# ESC.net
KiCad netlist of a schematic drawn in EAGLE
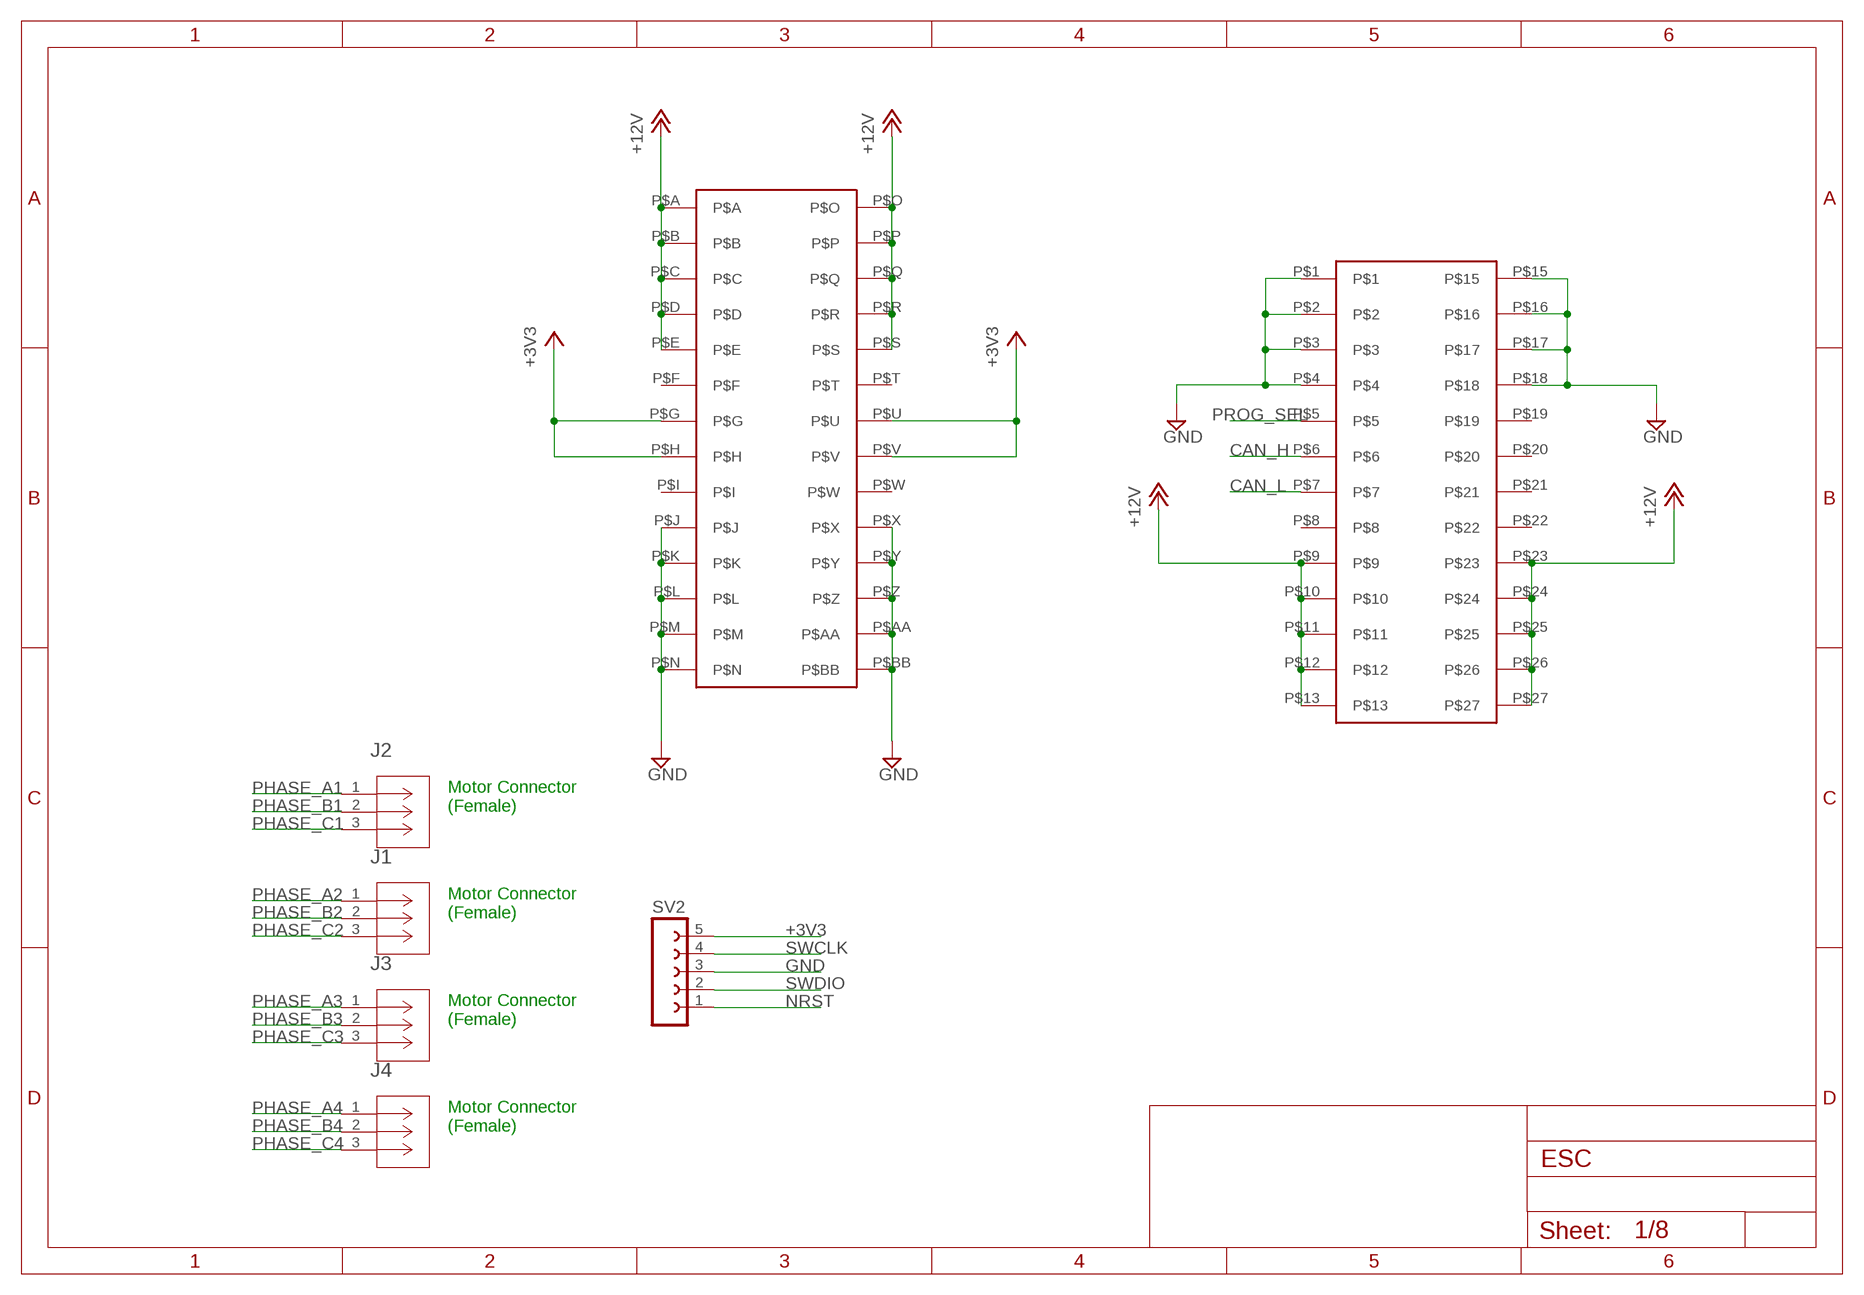
[diagram p0: schematic, sheet 1]
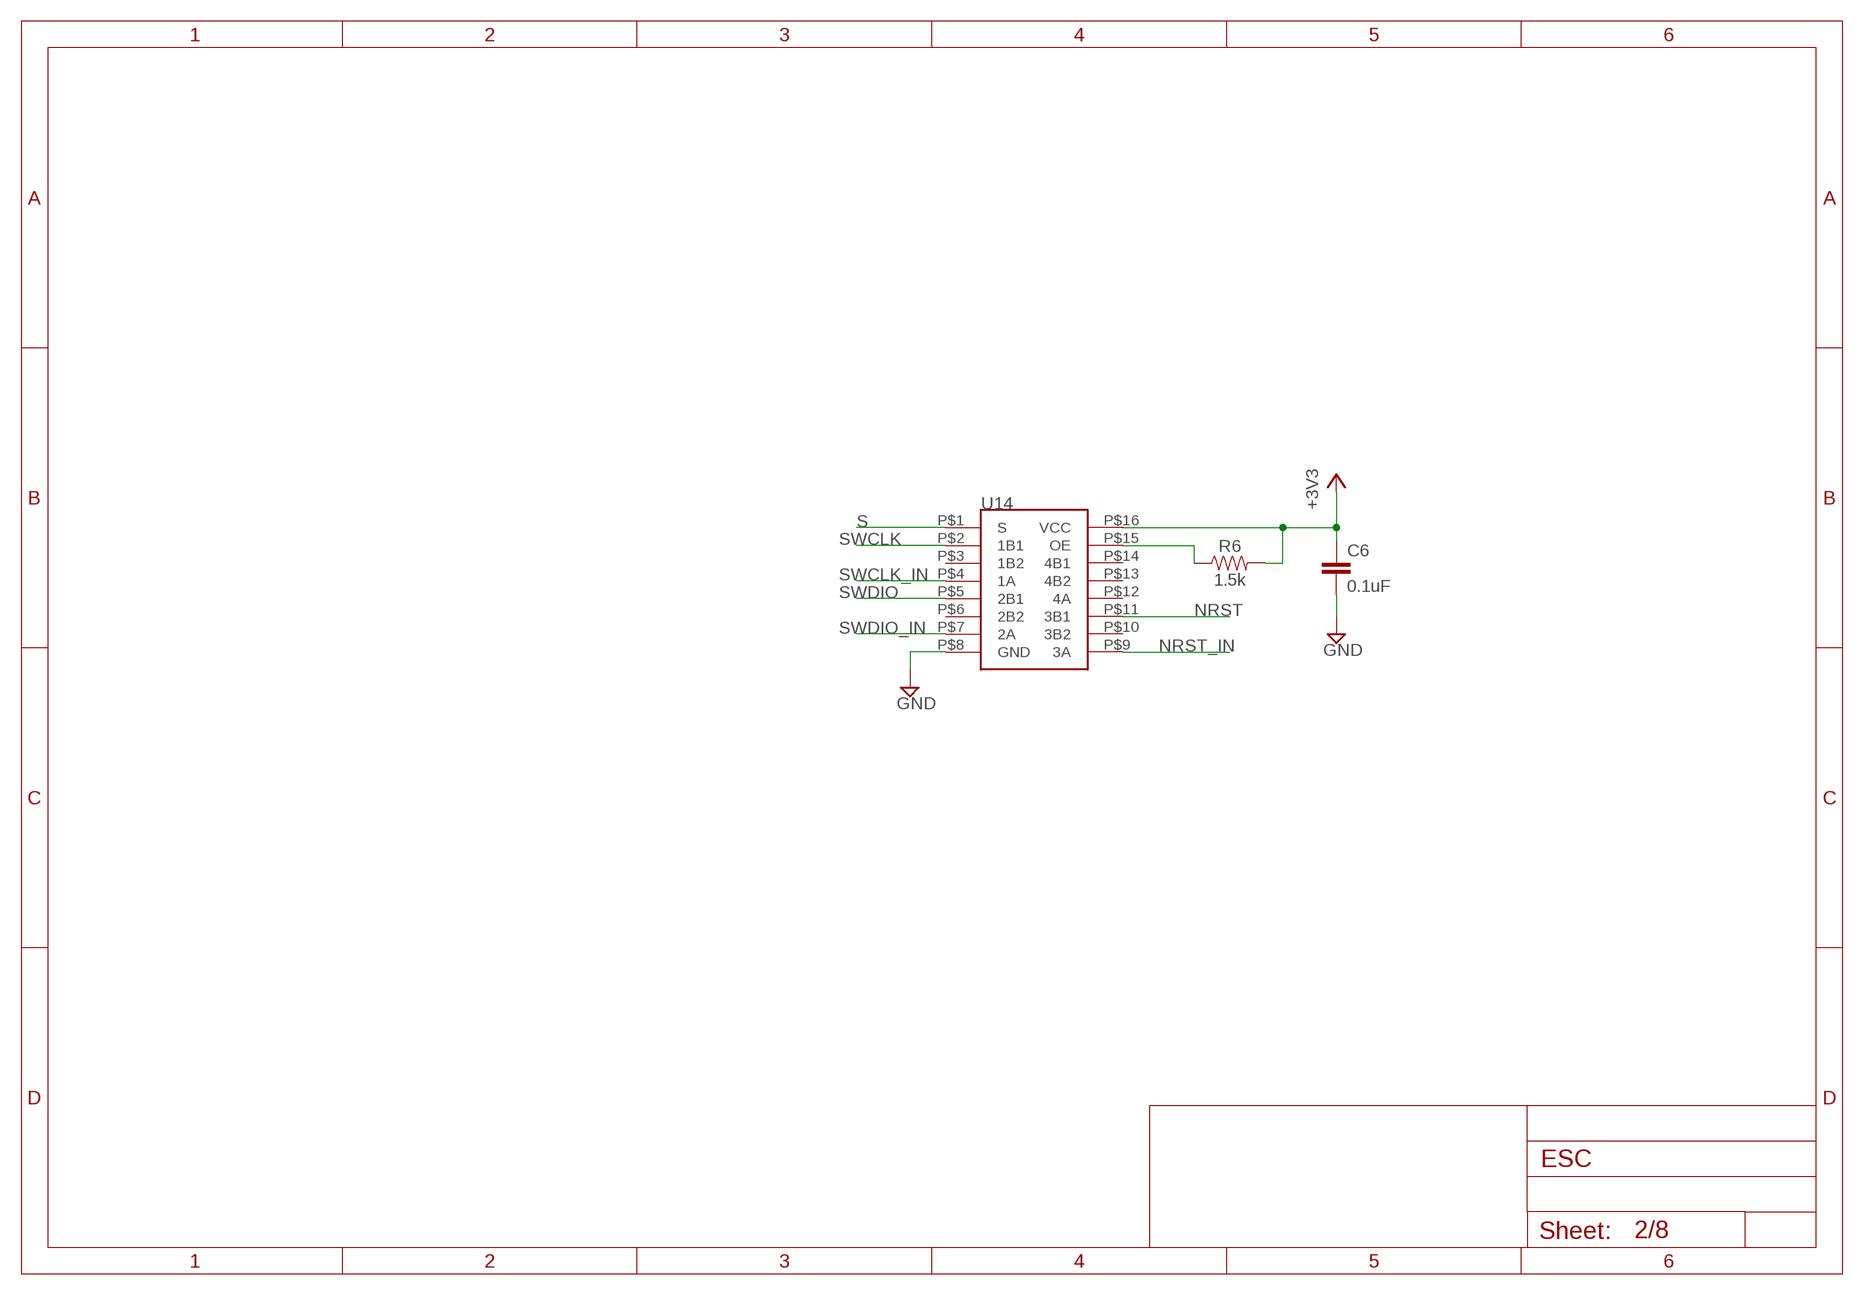
[diagram p1: schematic, sheet 2]
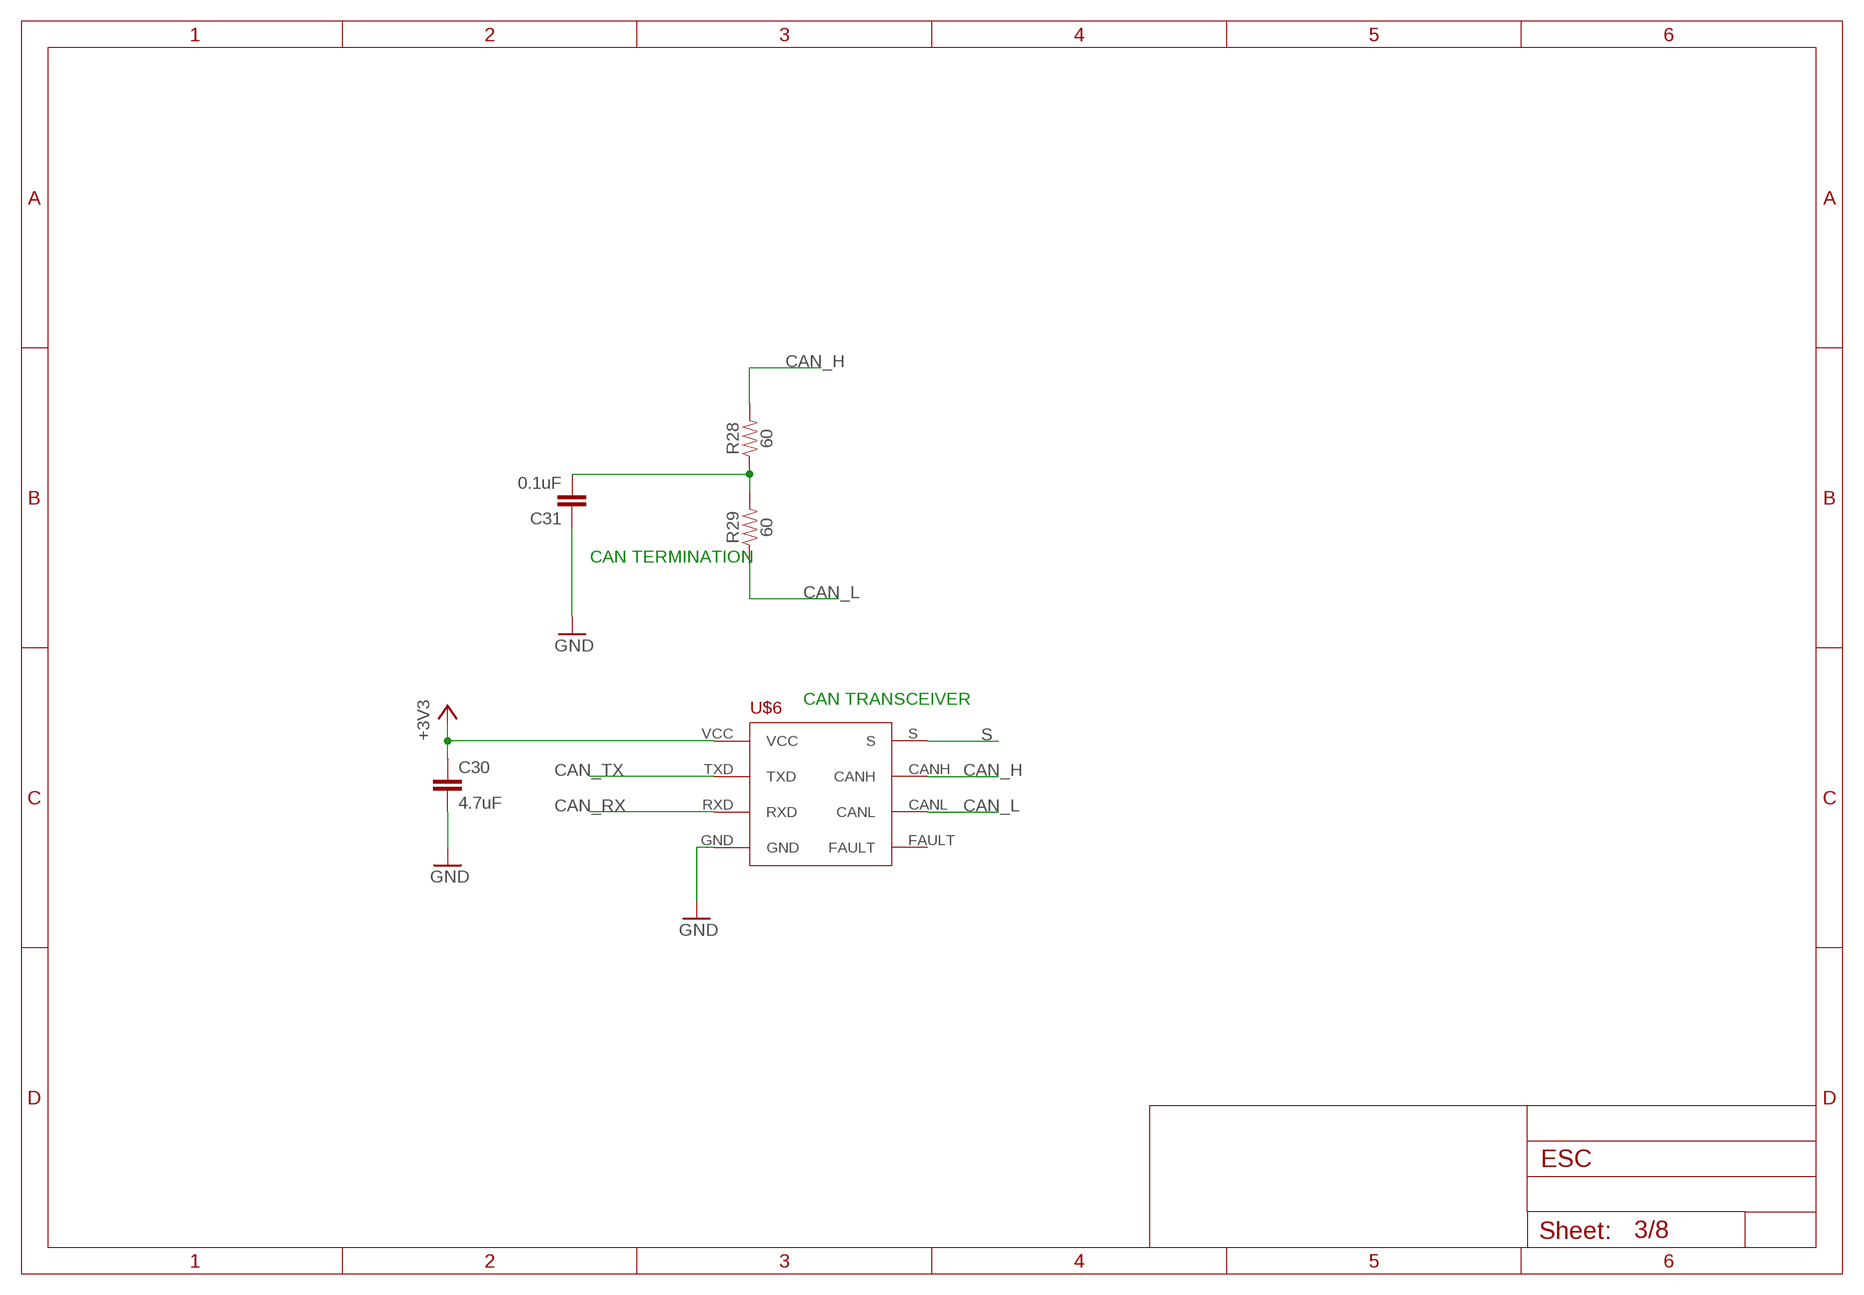
[diagram p2: schematic, sheet 3]
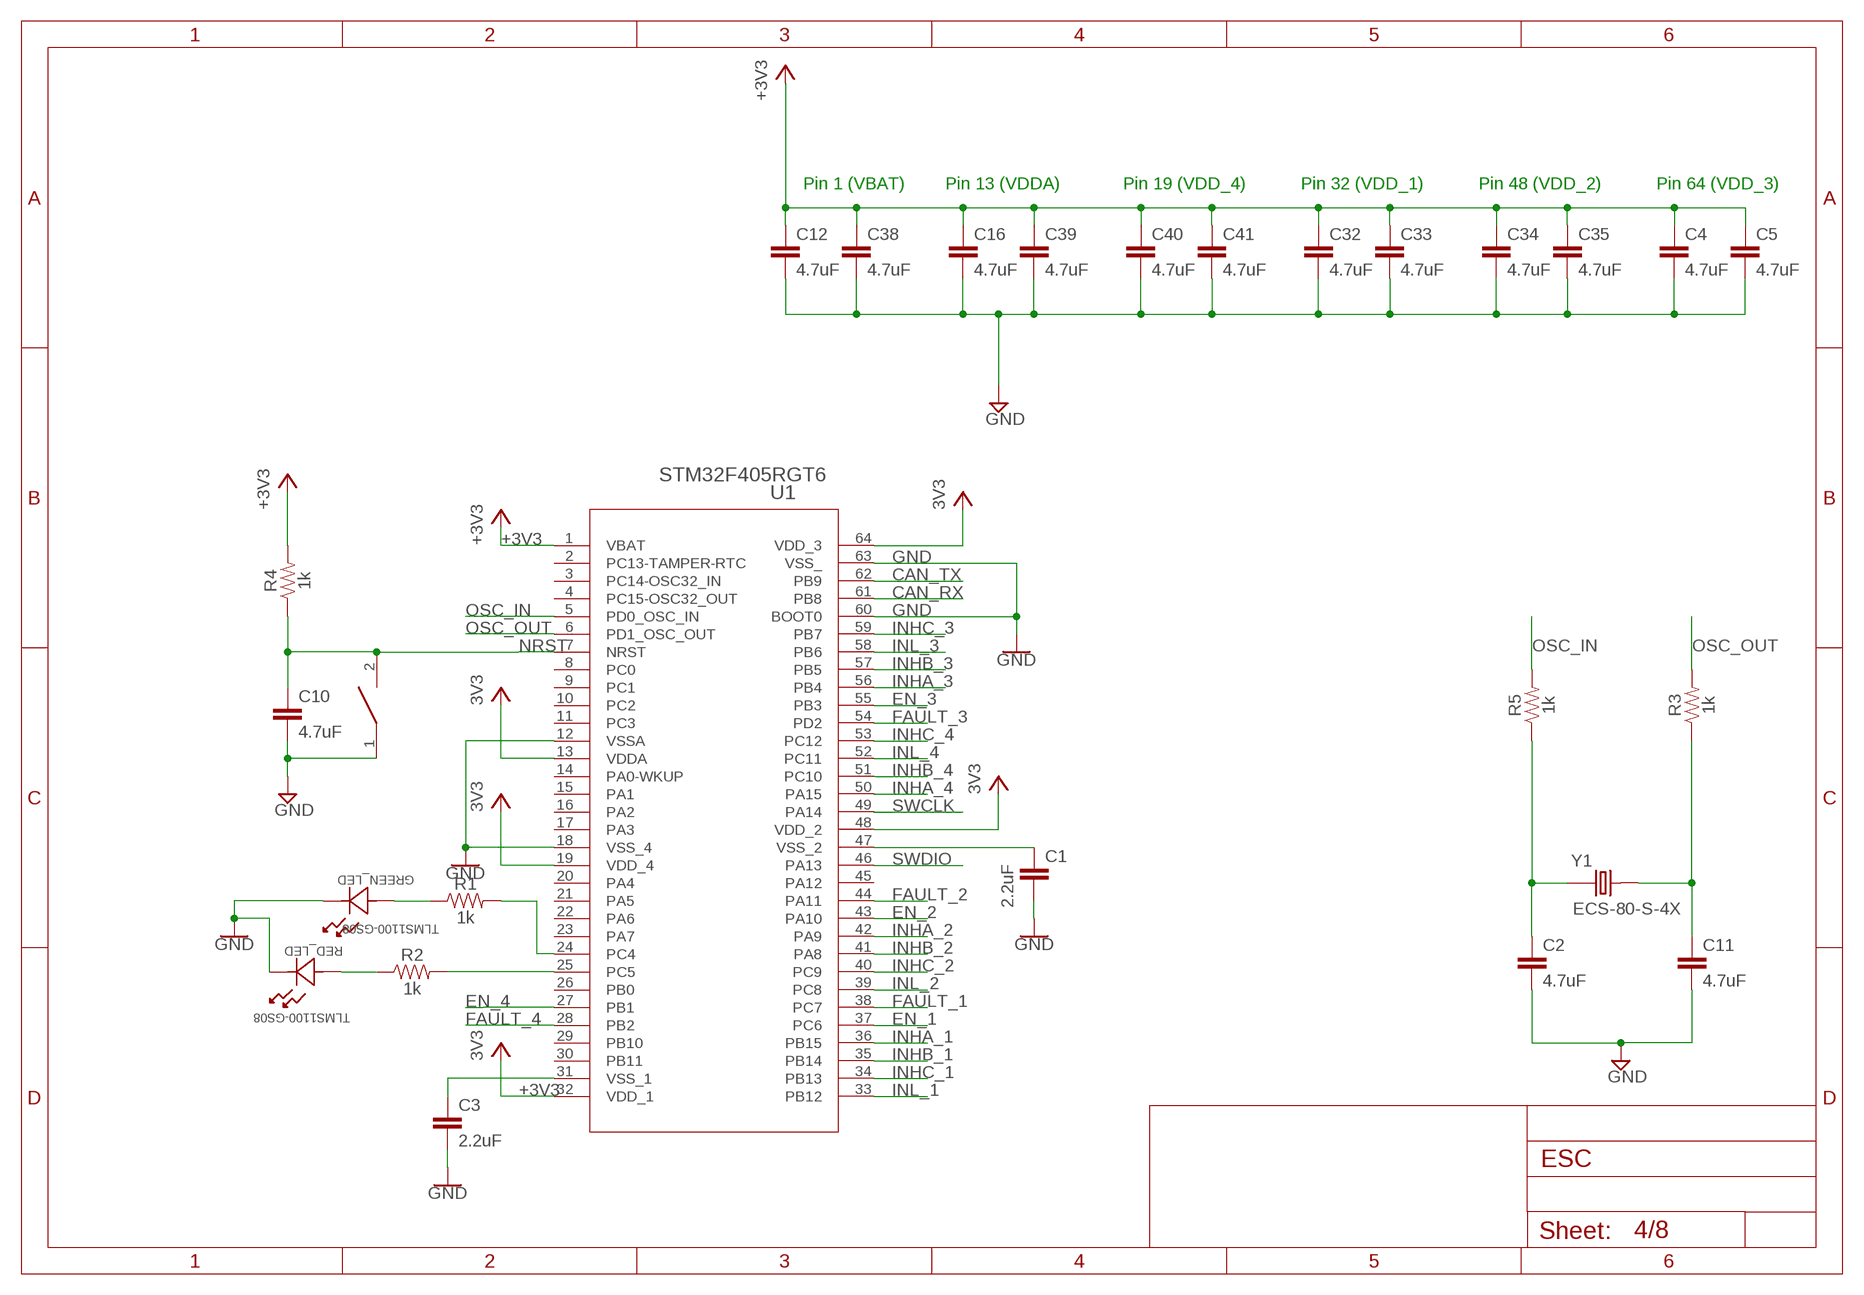
[diagram p3: schematic, sheet 4]
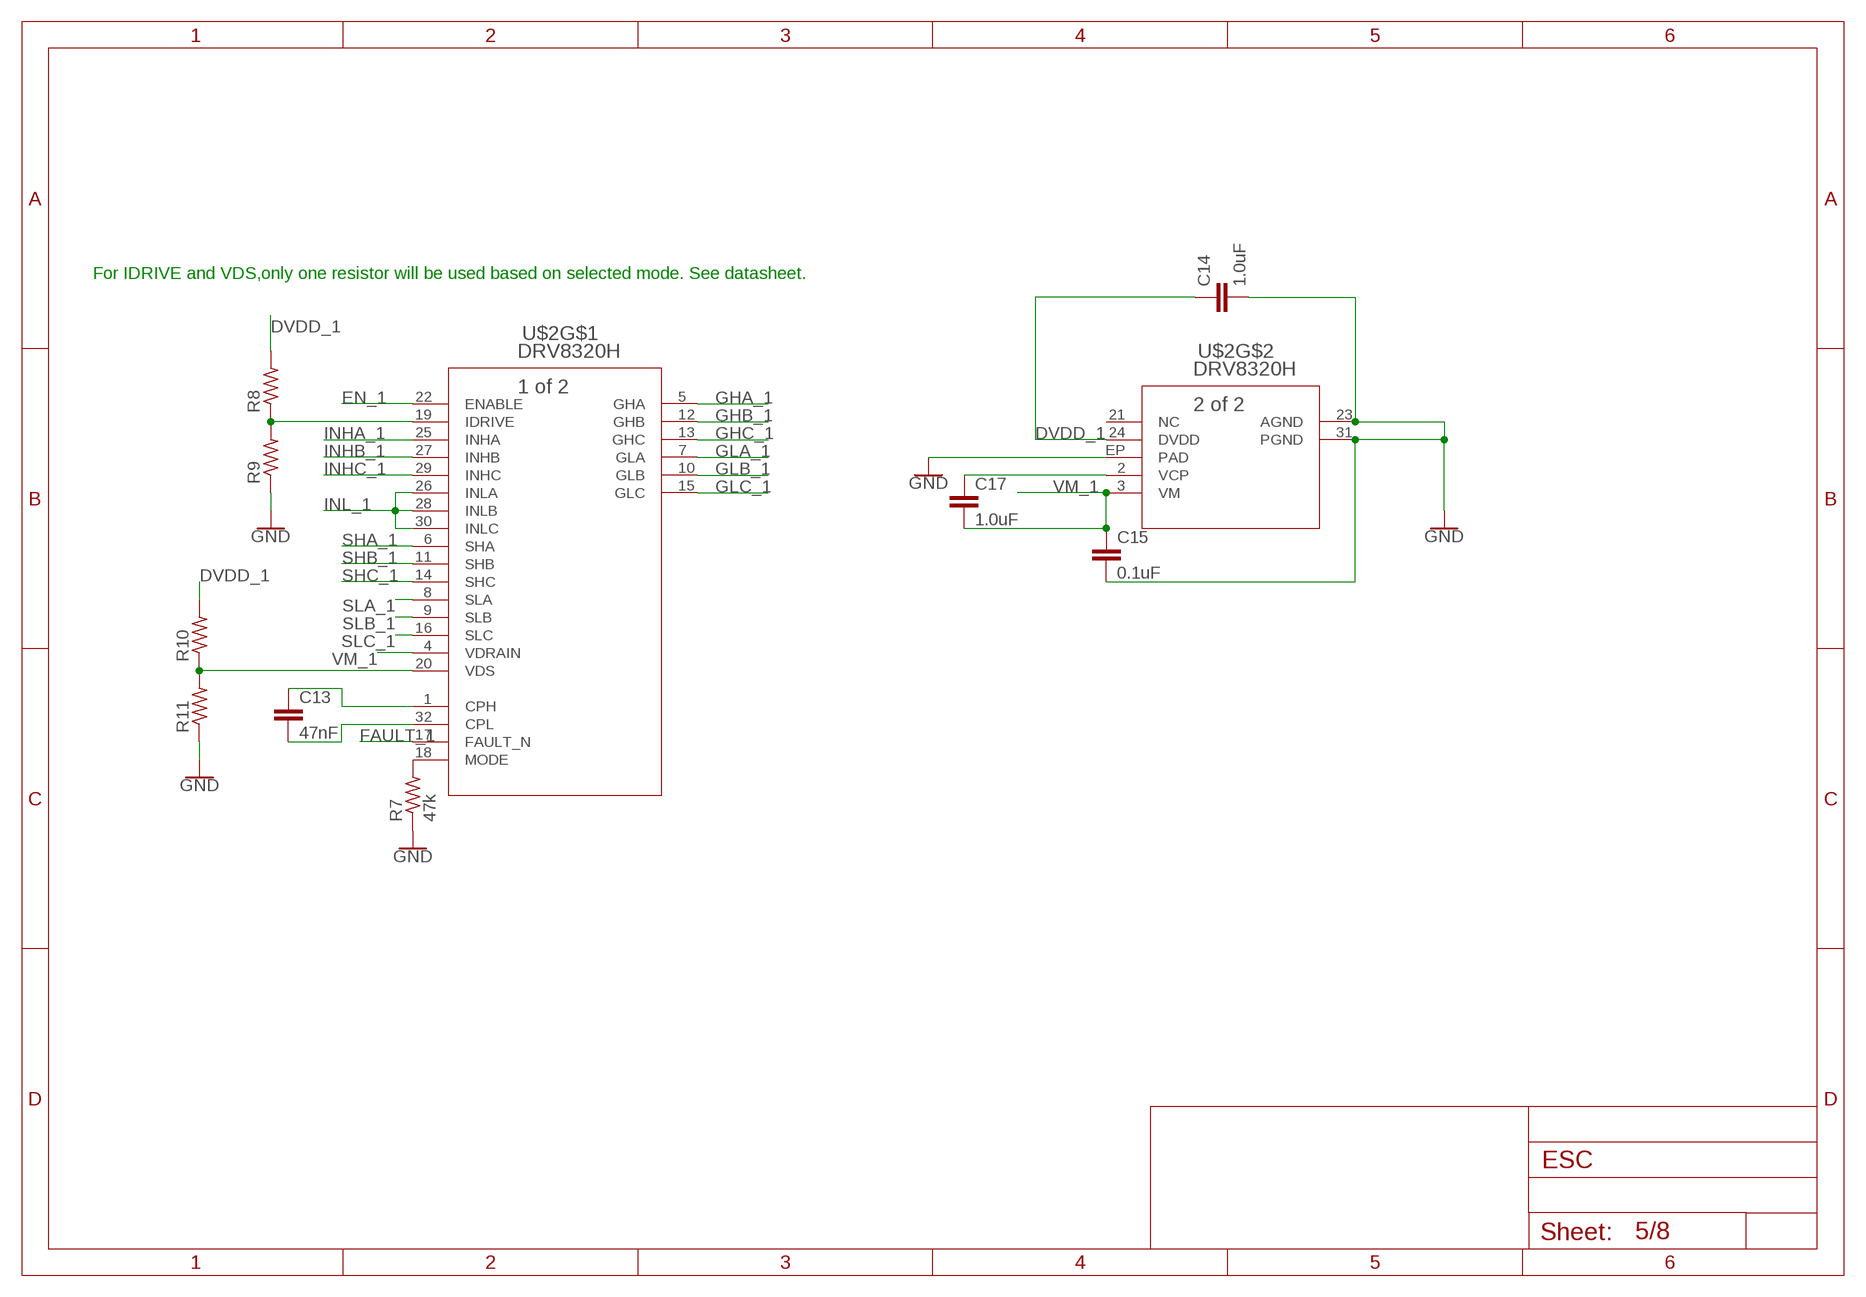
[diagram p4: schematic, sheet 5, part 1 of 2]
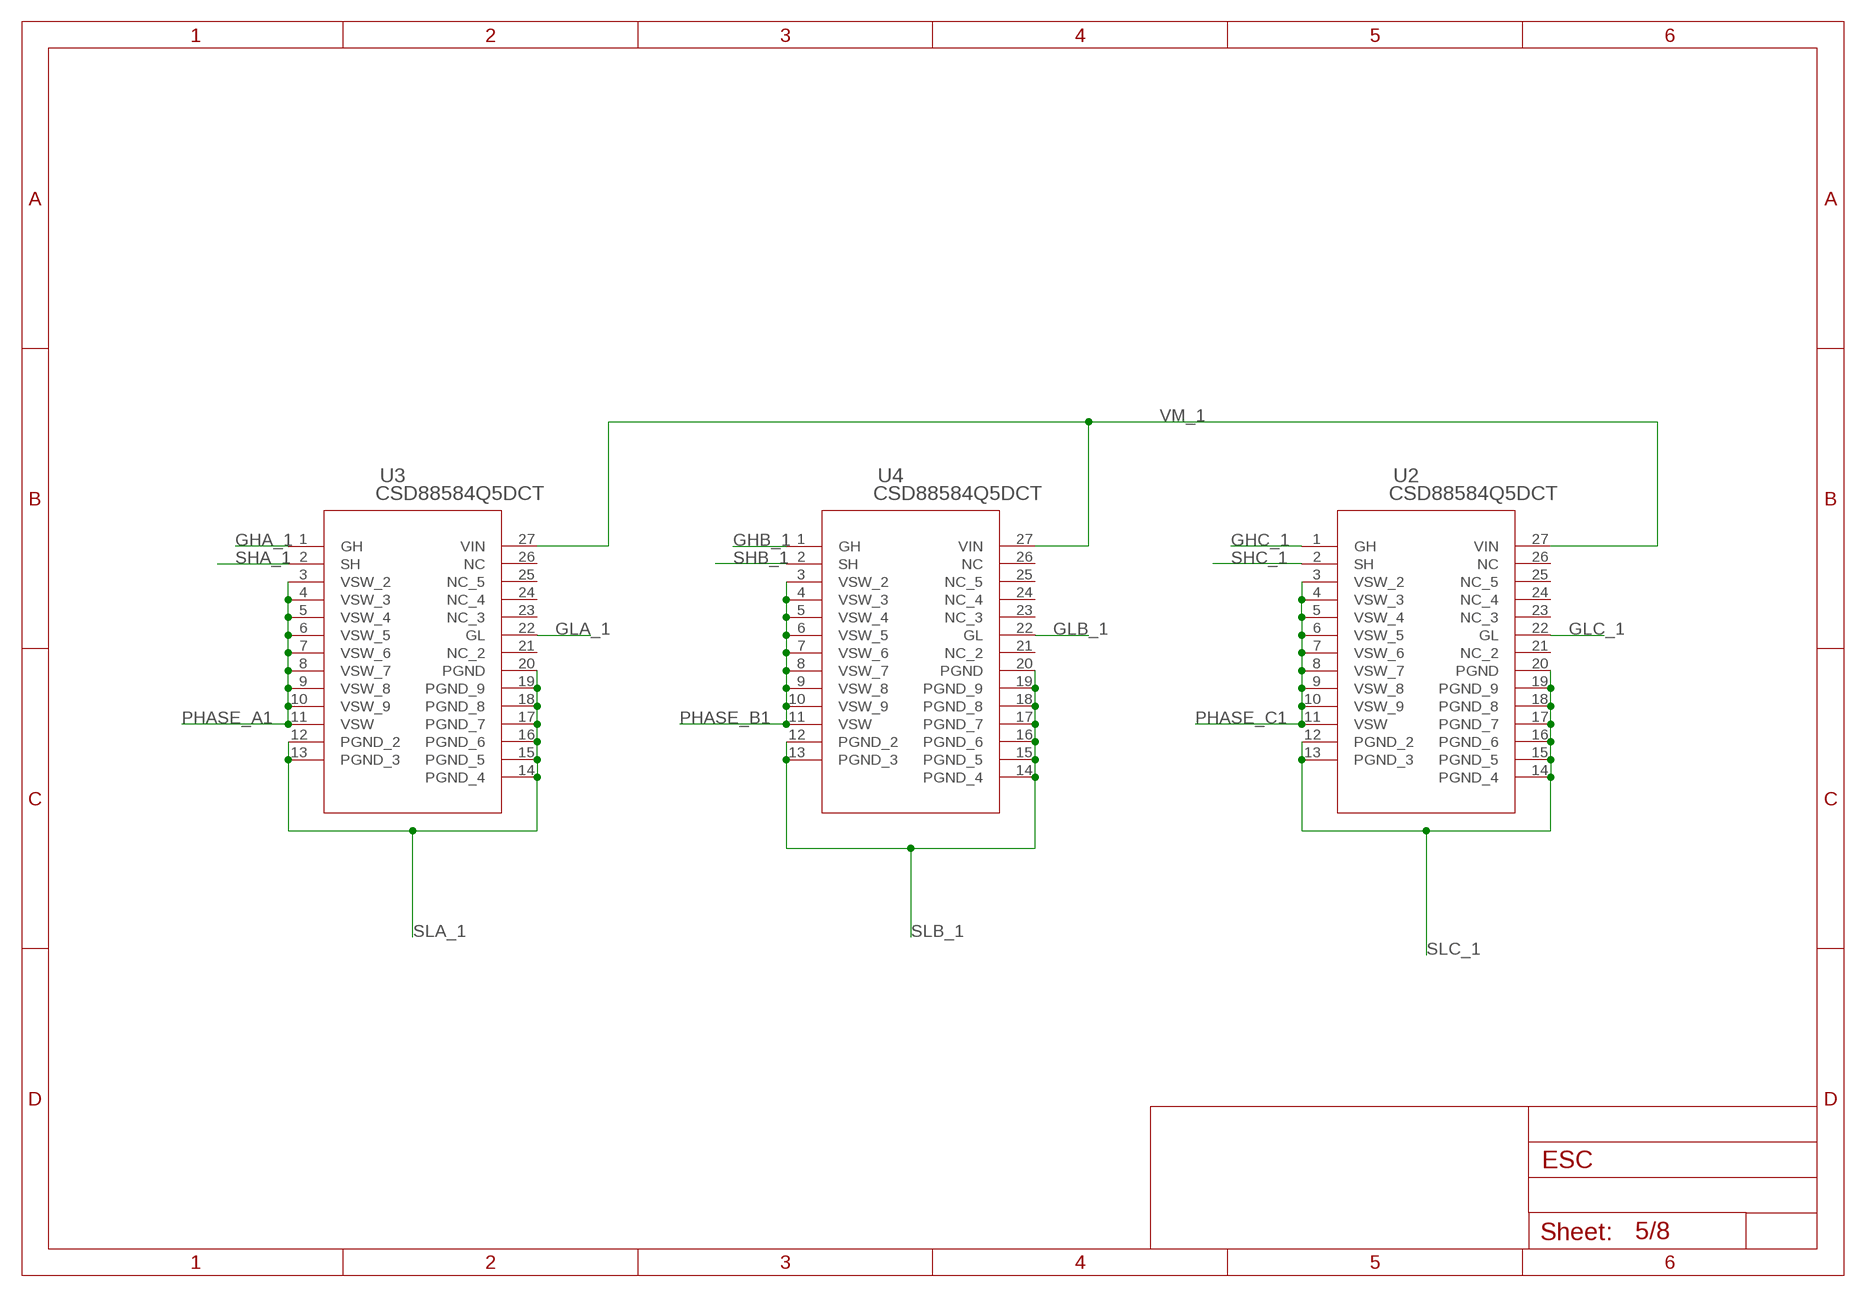
[diagram p5: schematic, sheet 5, part 2 of 2]
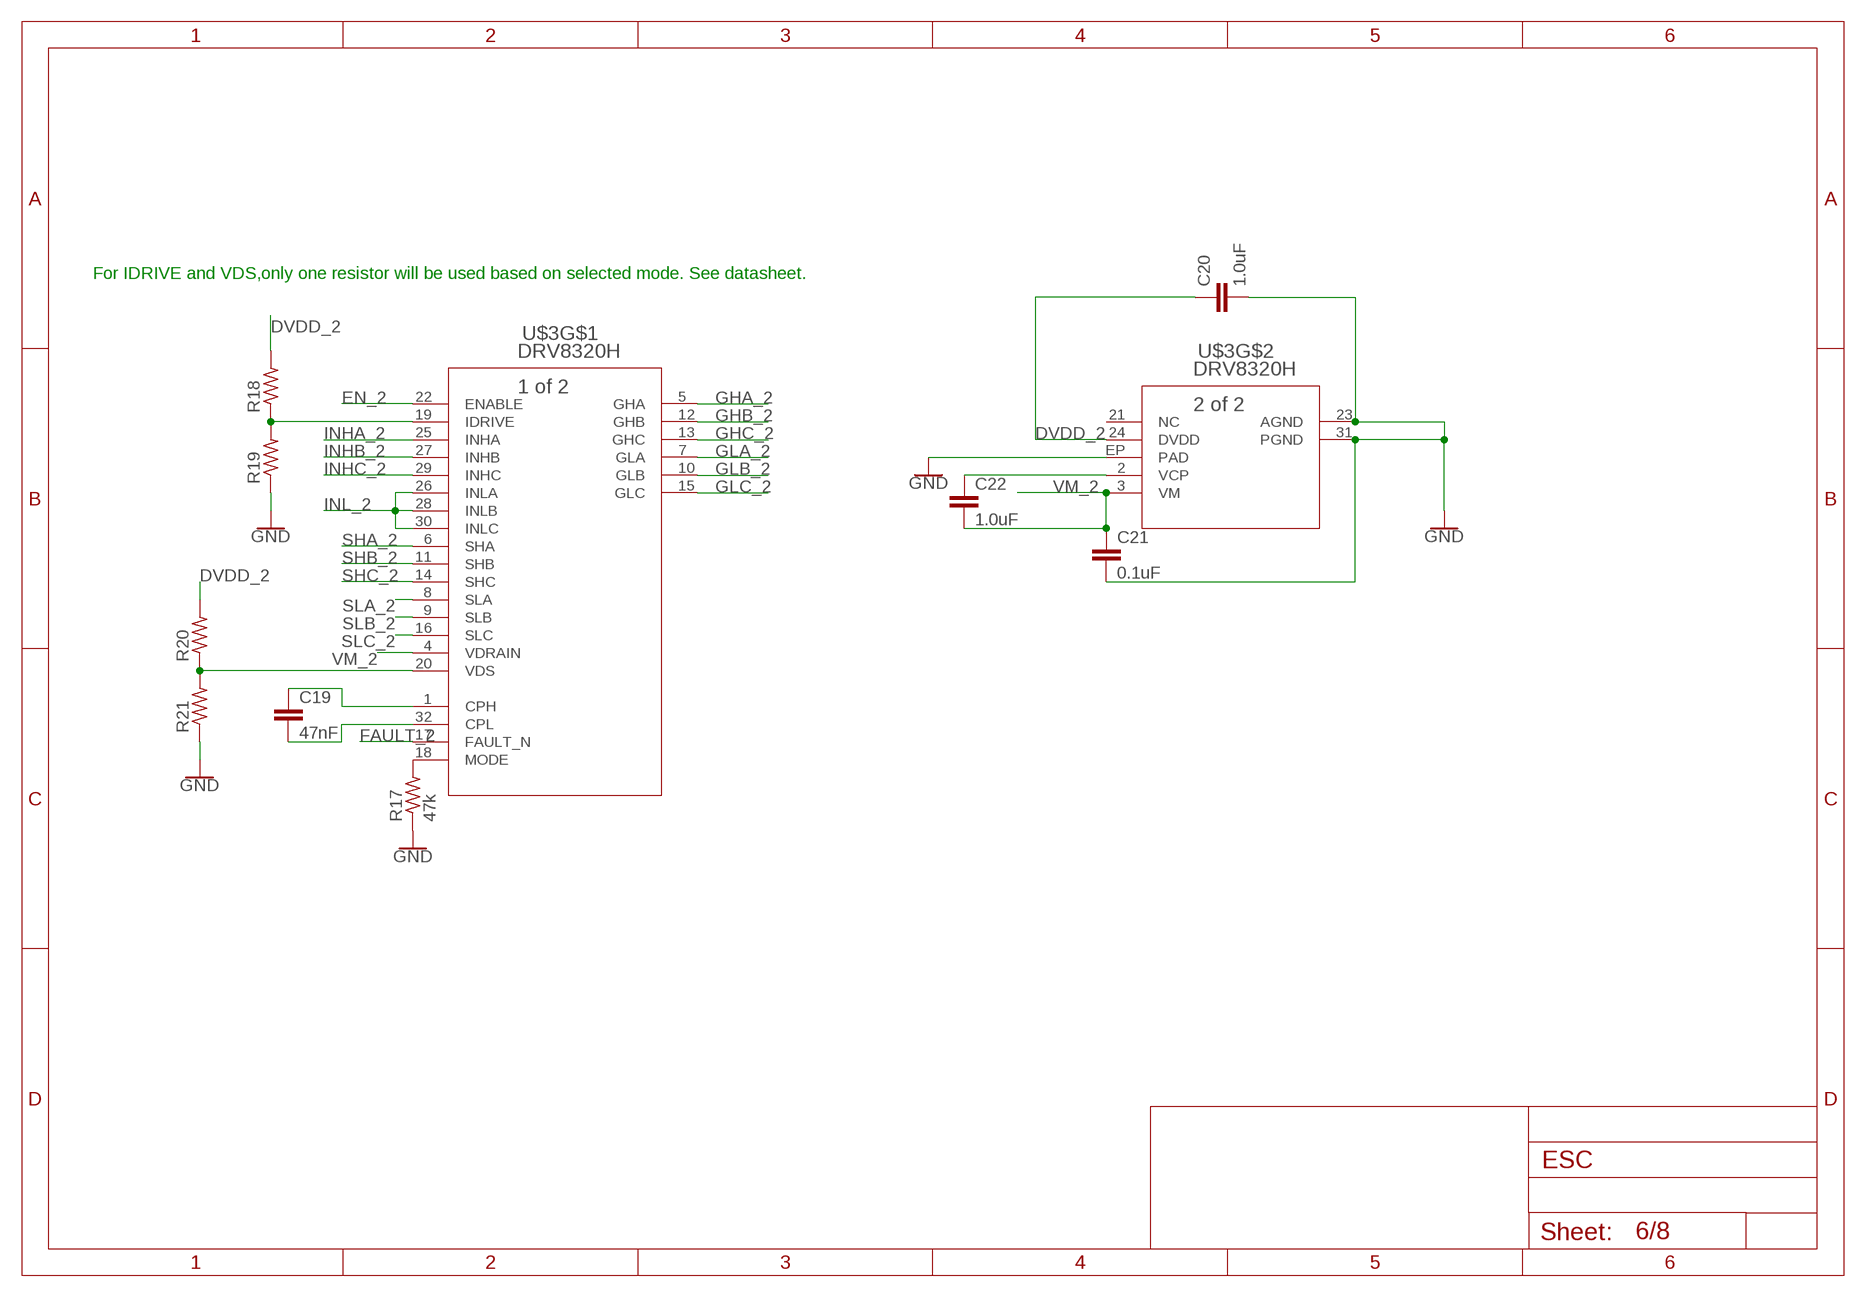
[diagram p6: schematic, sheet 6, part 1 of 2]
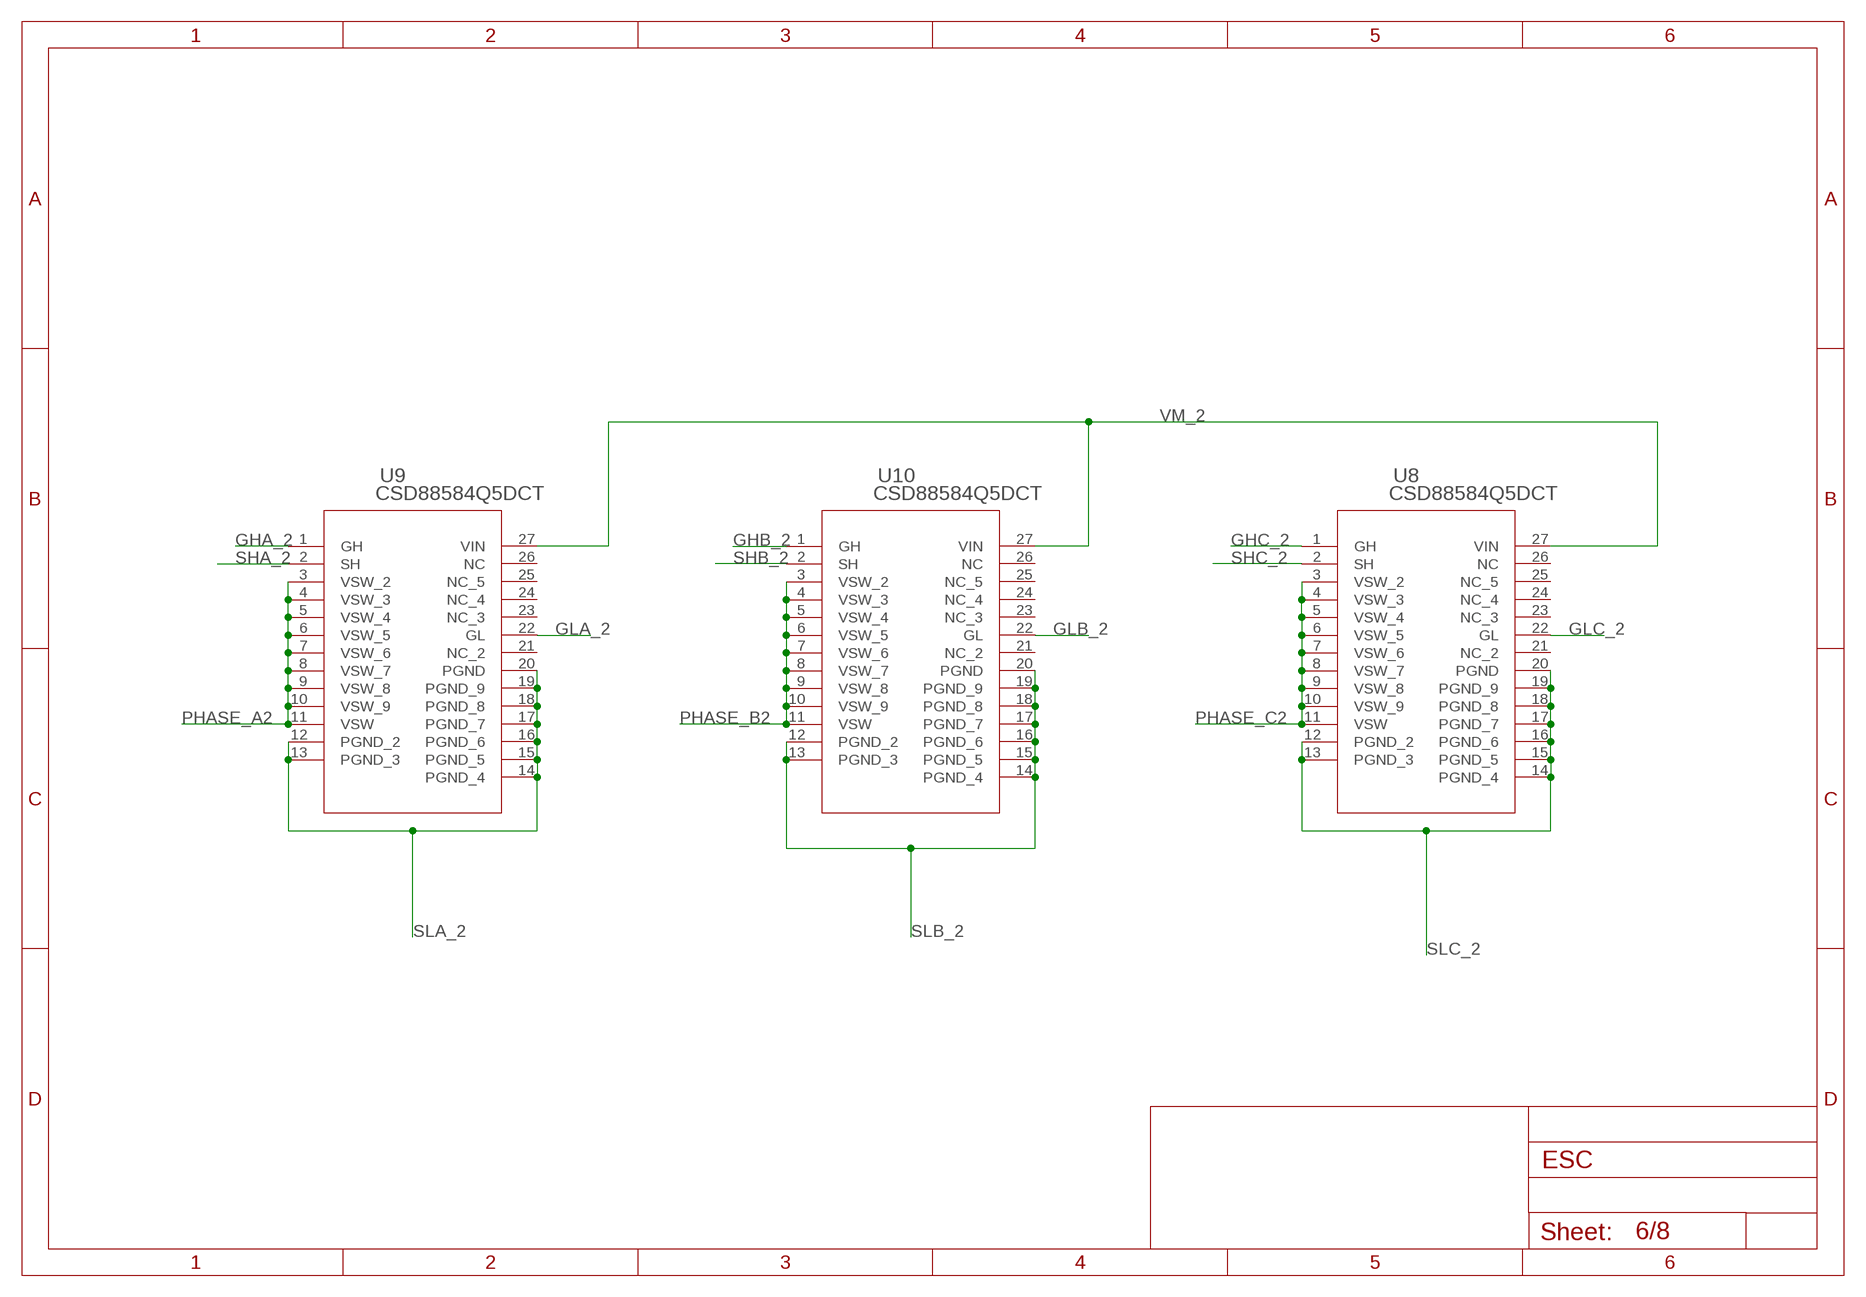
[diagram p7: schematic, sheet 6, part 2 of 2]
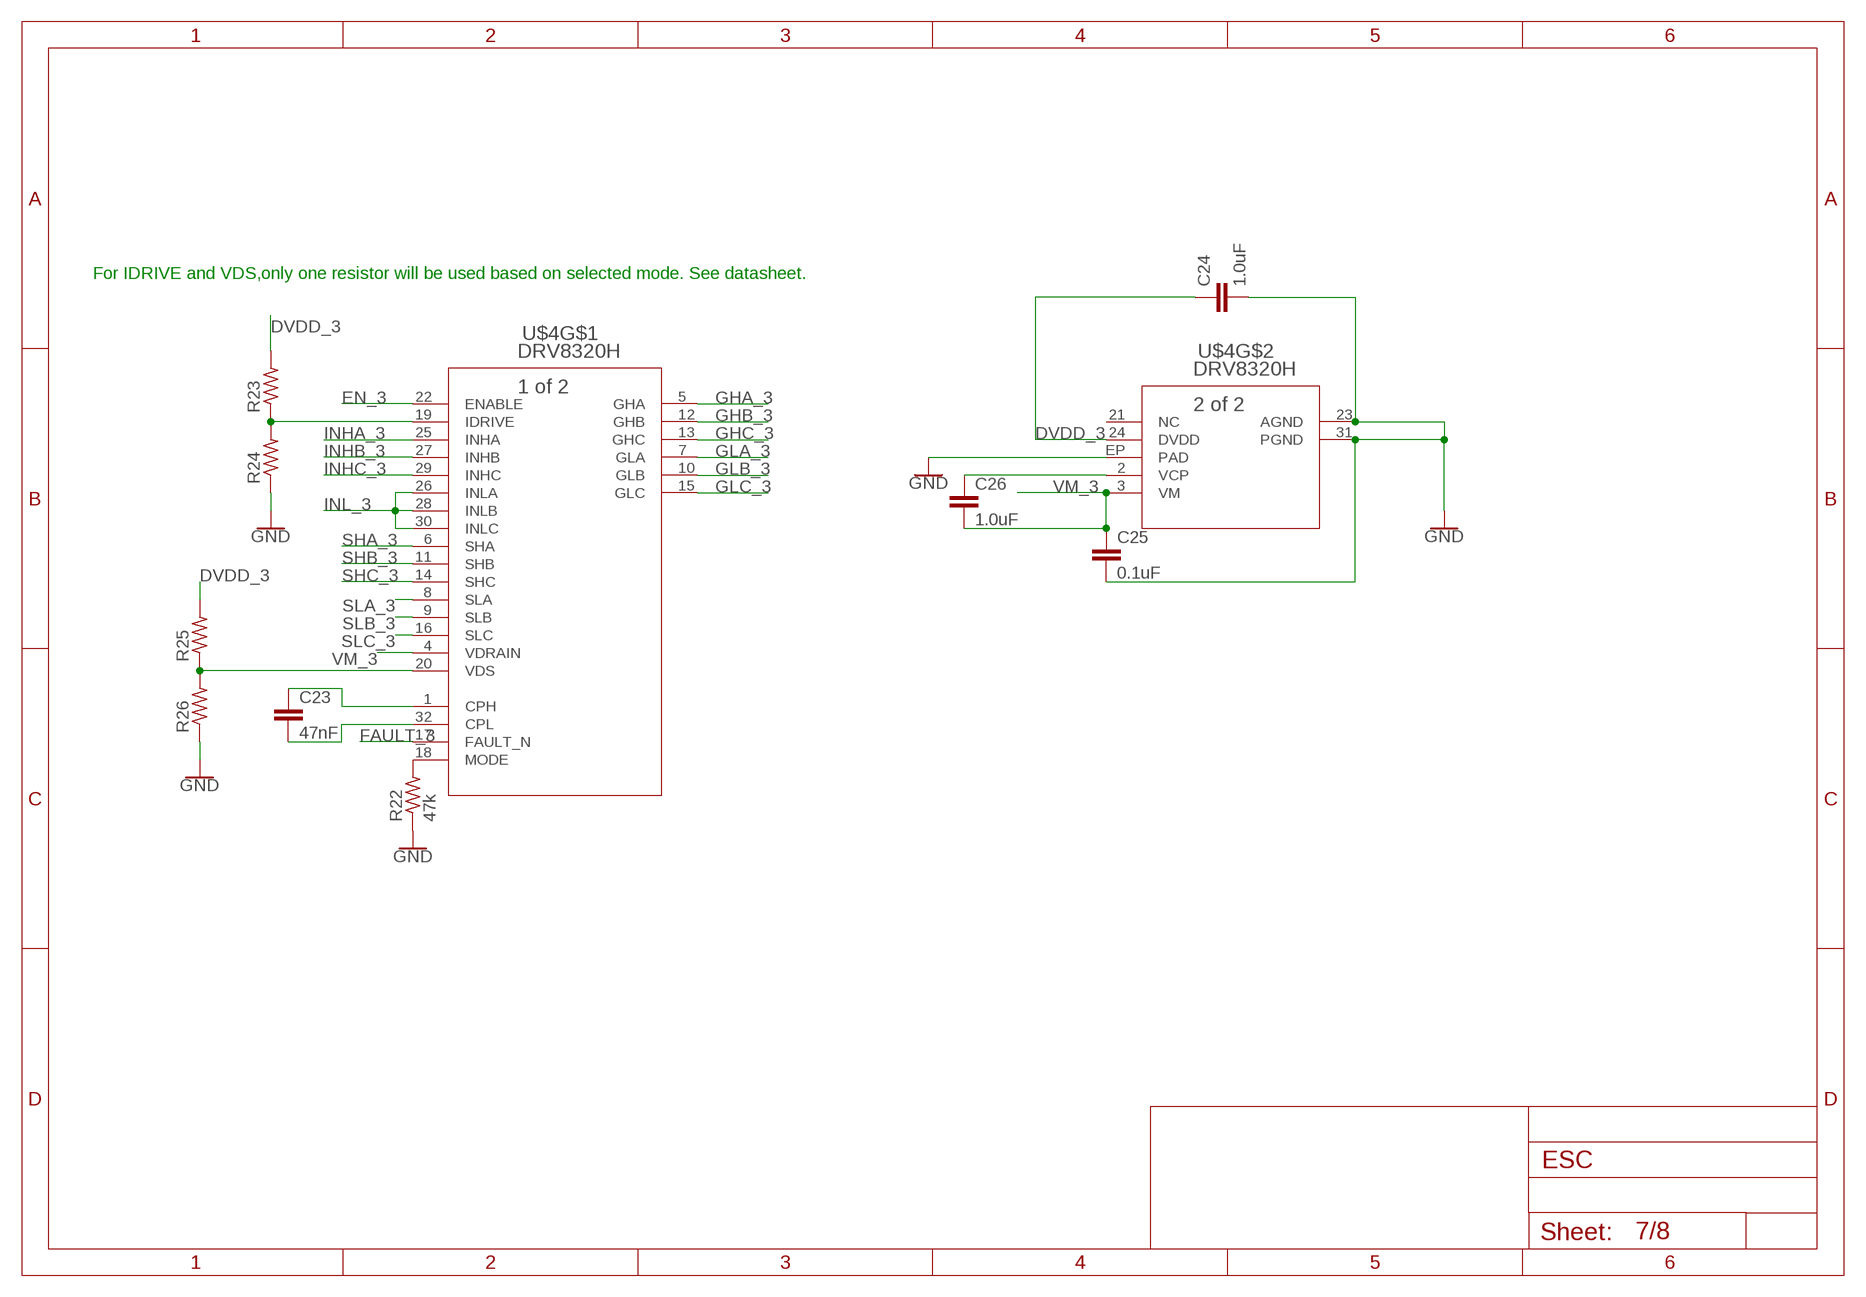
[diagram p8: schematic, sheet 7, part 1 of 2]
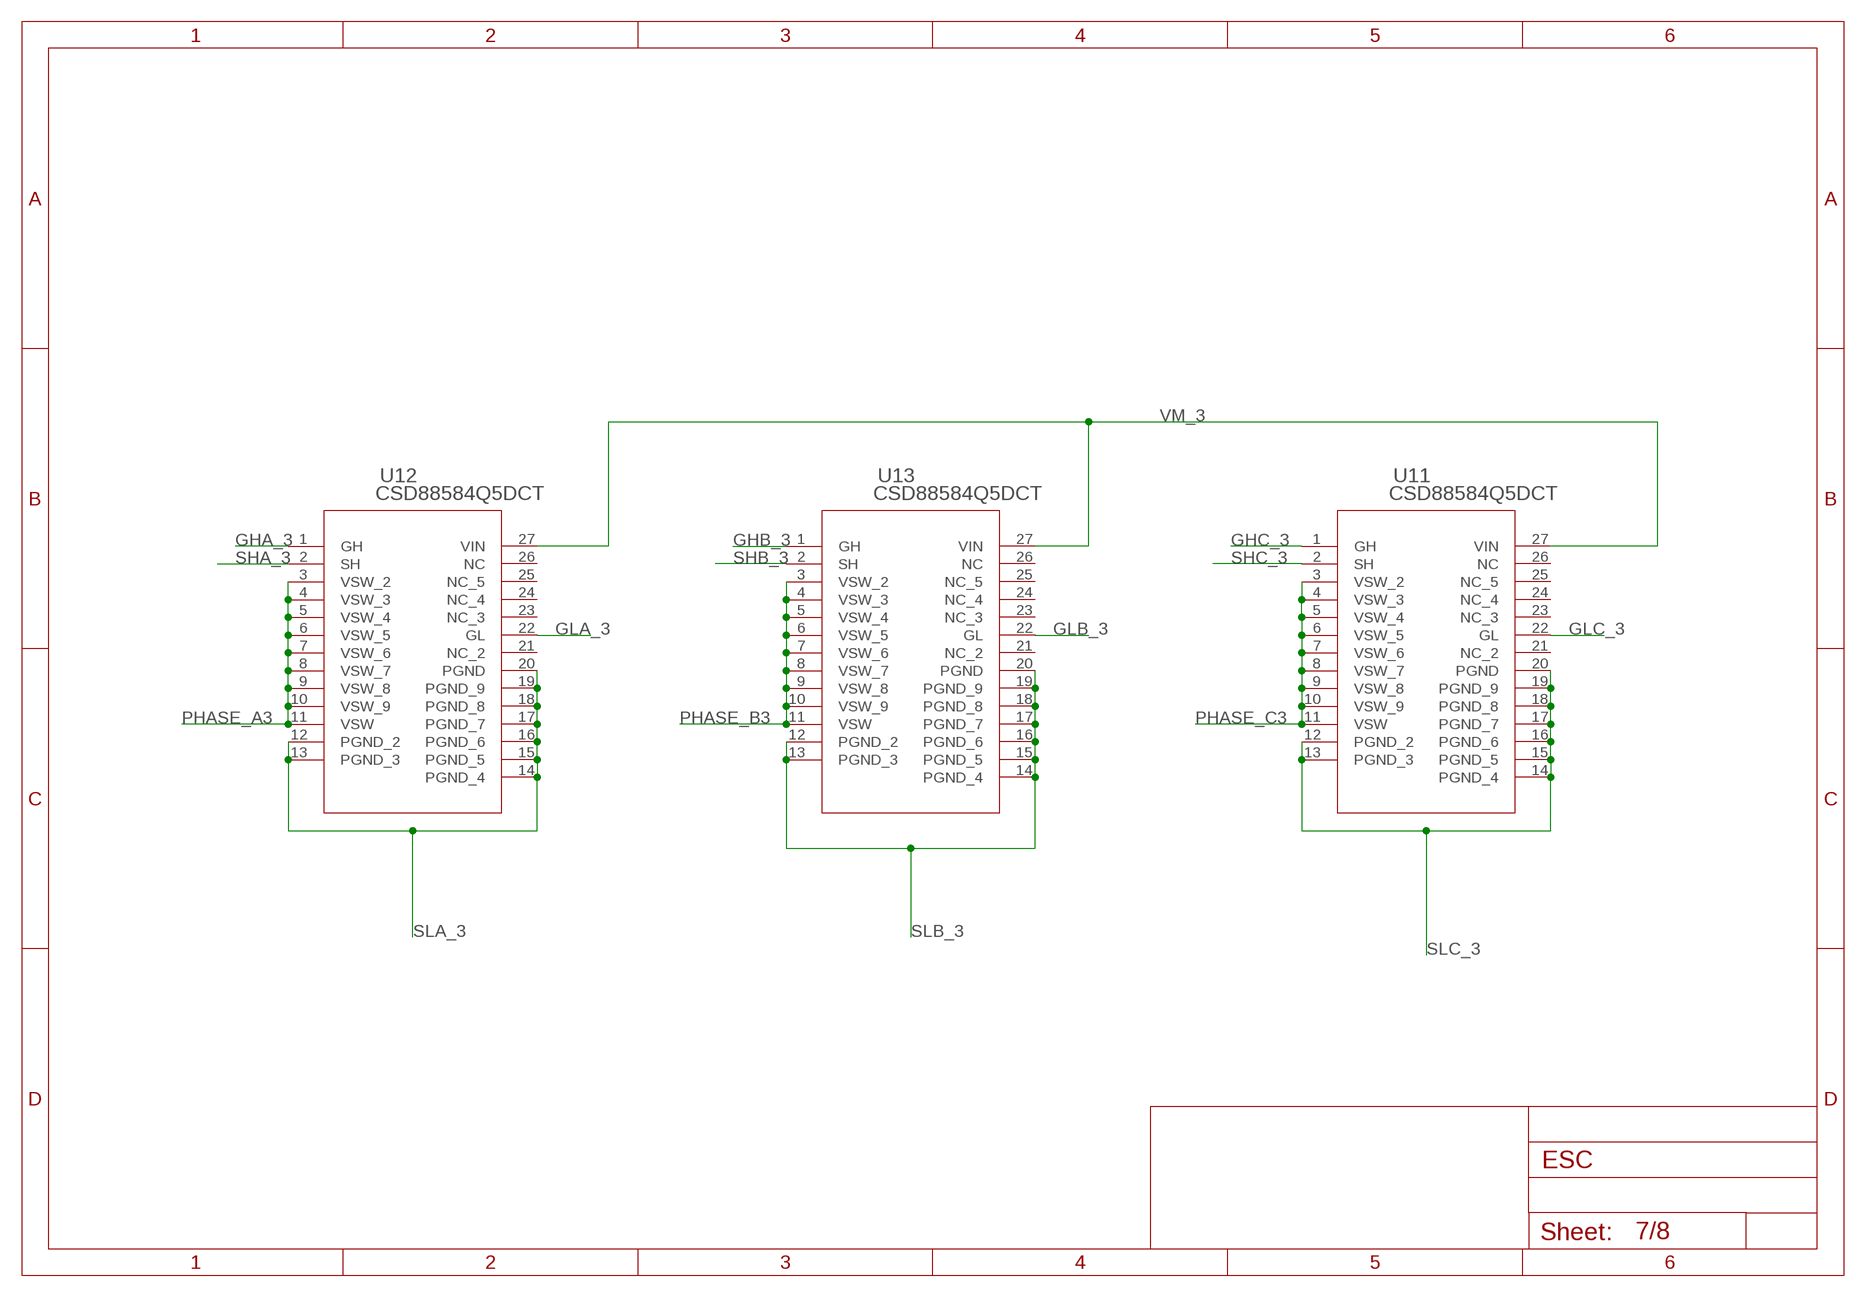
[diagram p9: schematic, sheet 7, part 2 of 2]
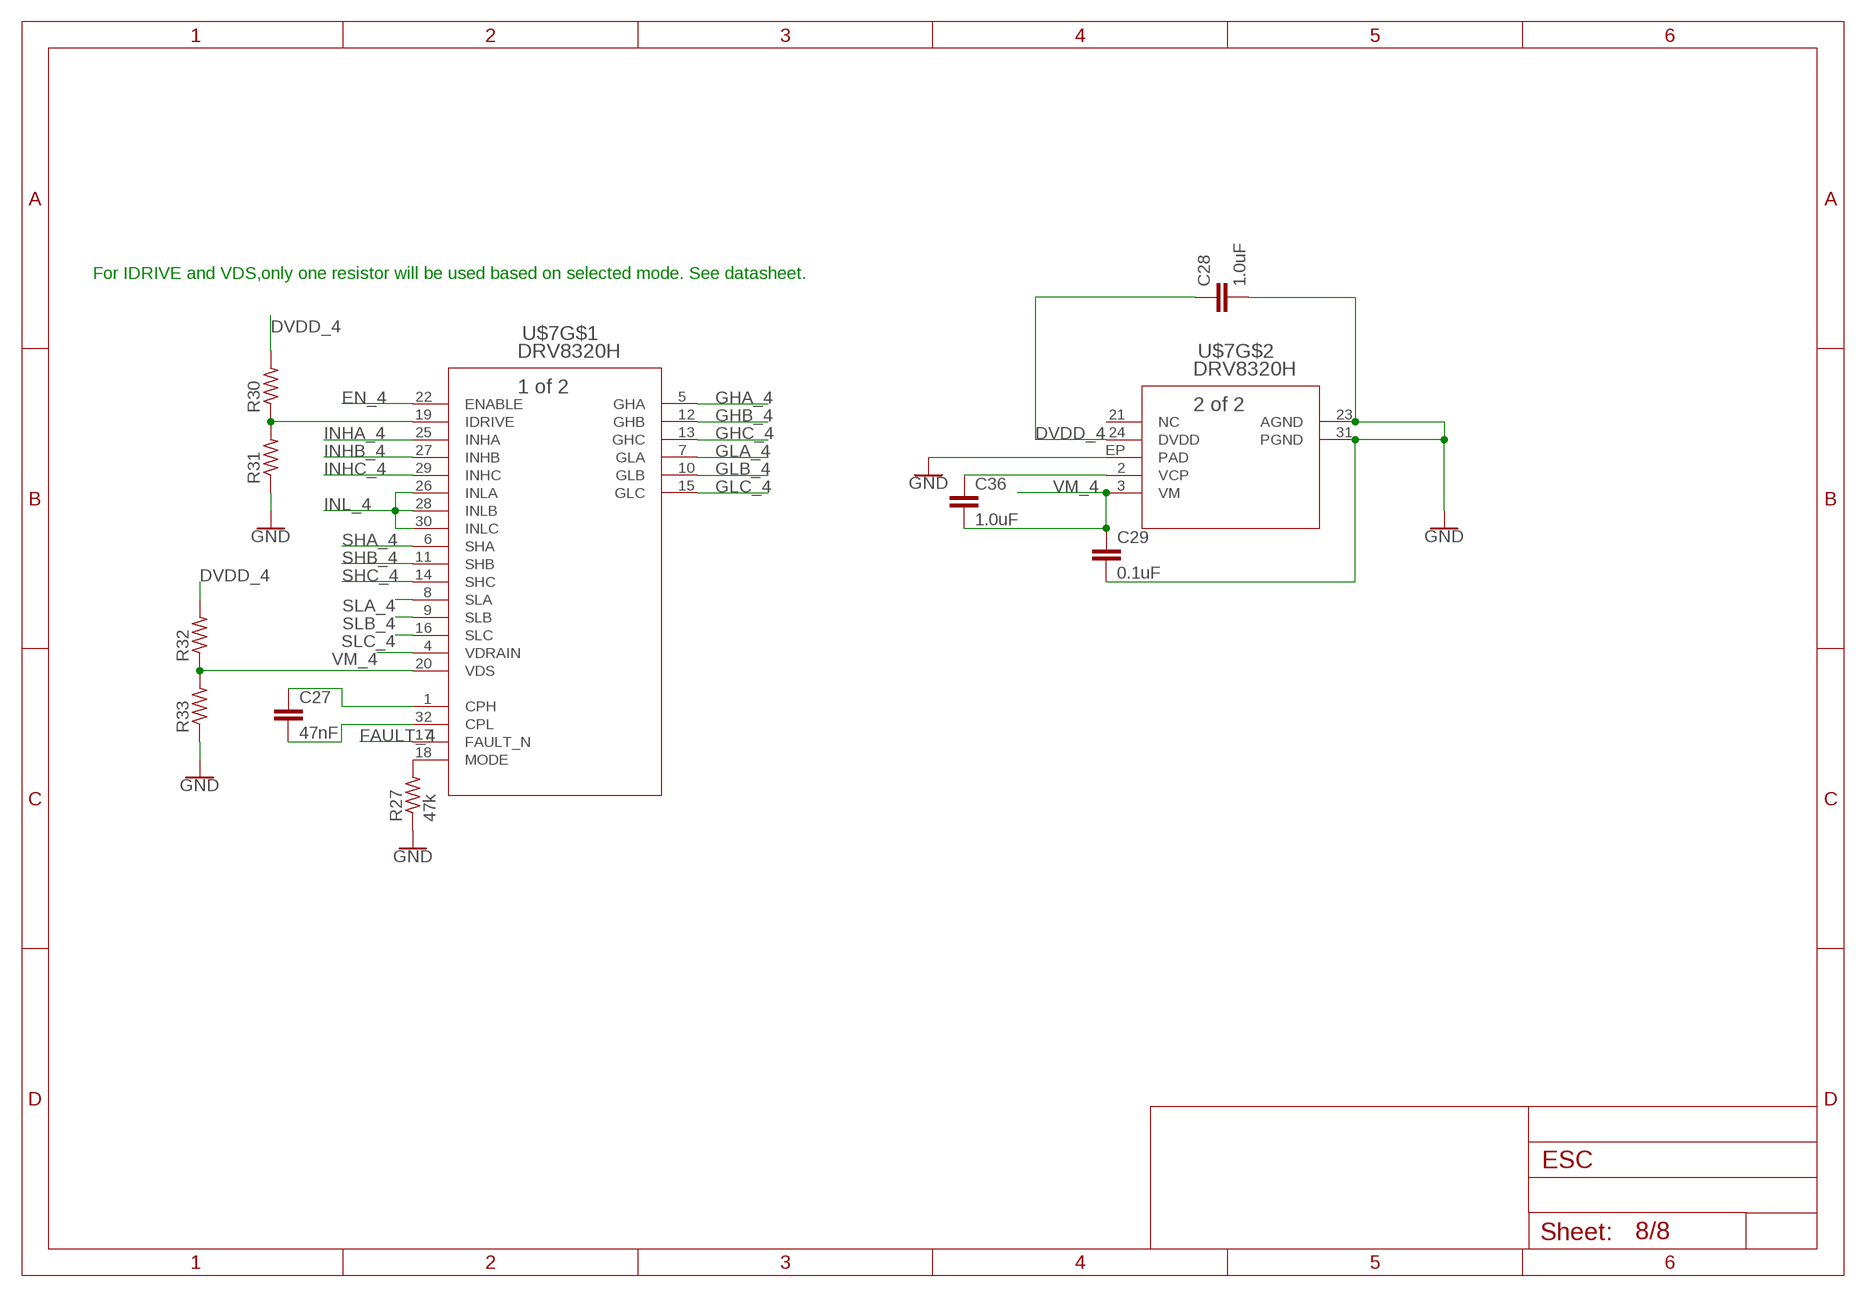
[diagram p10: schematic, sheet 8, part 1 of 2]
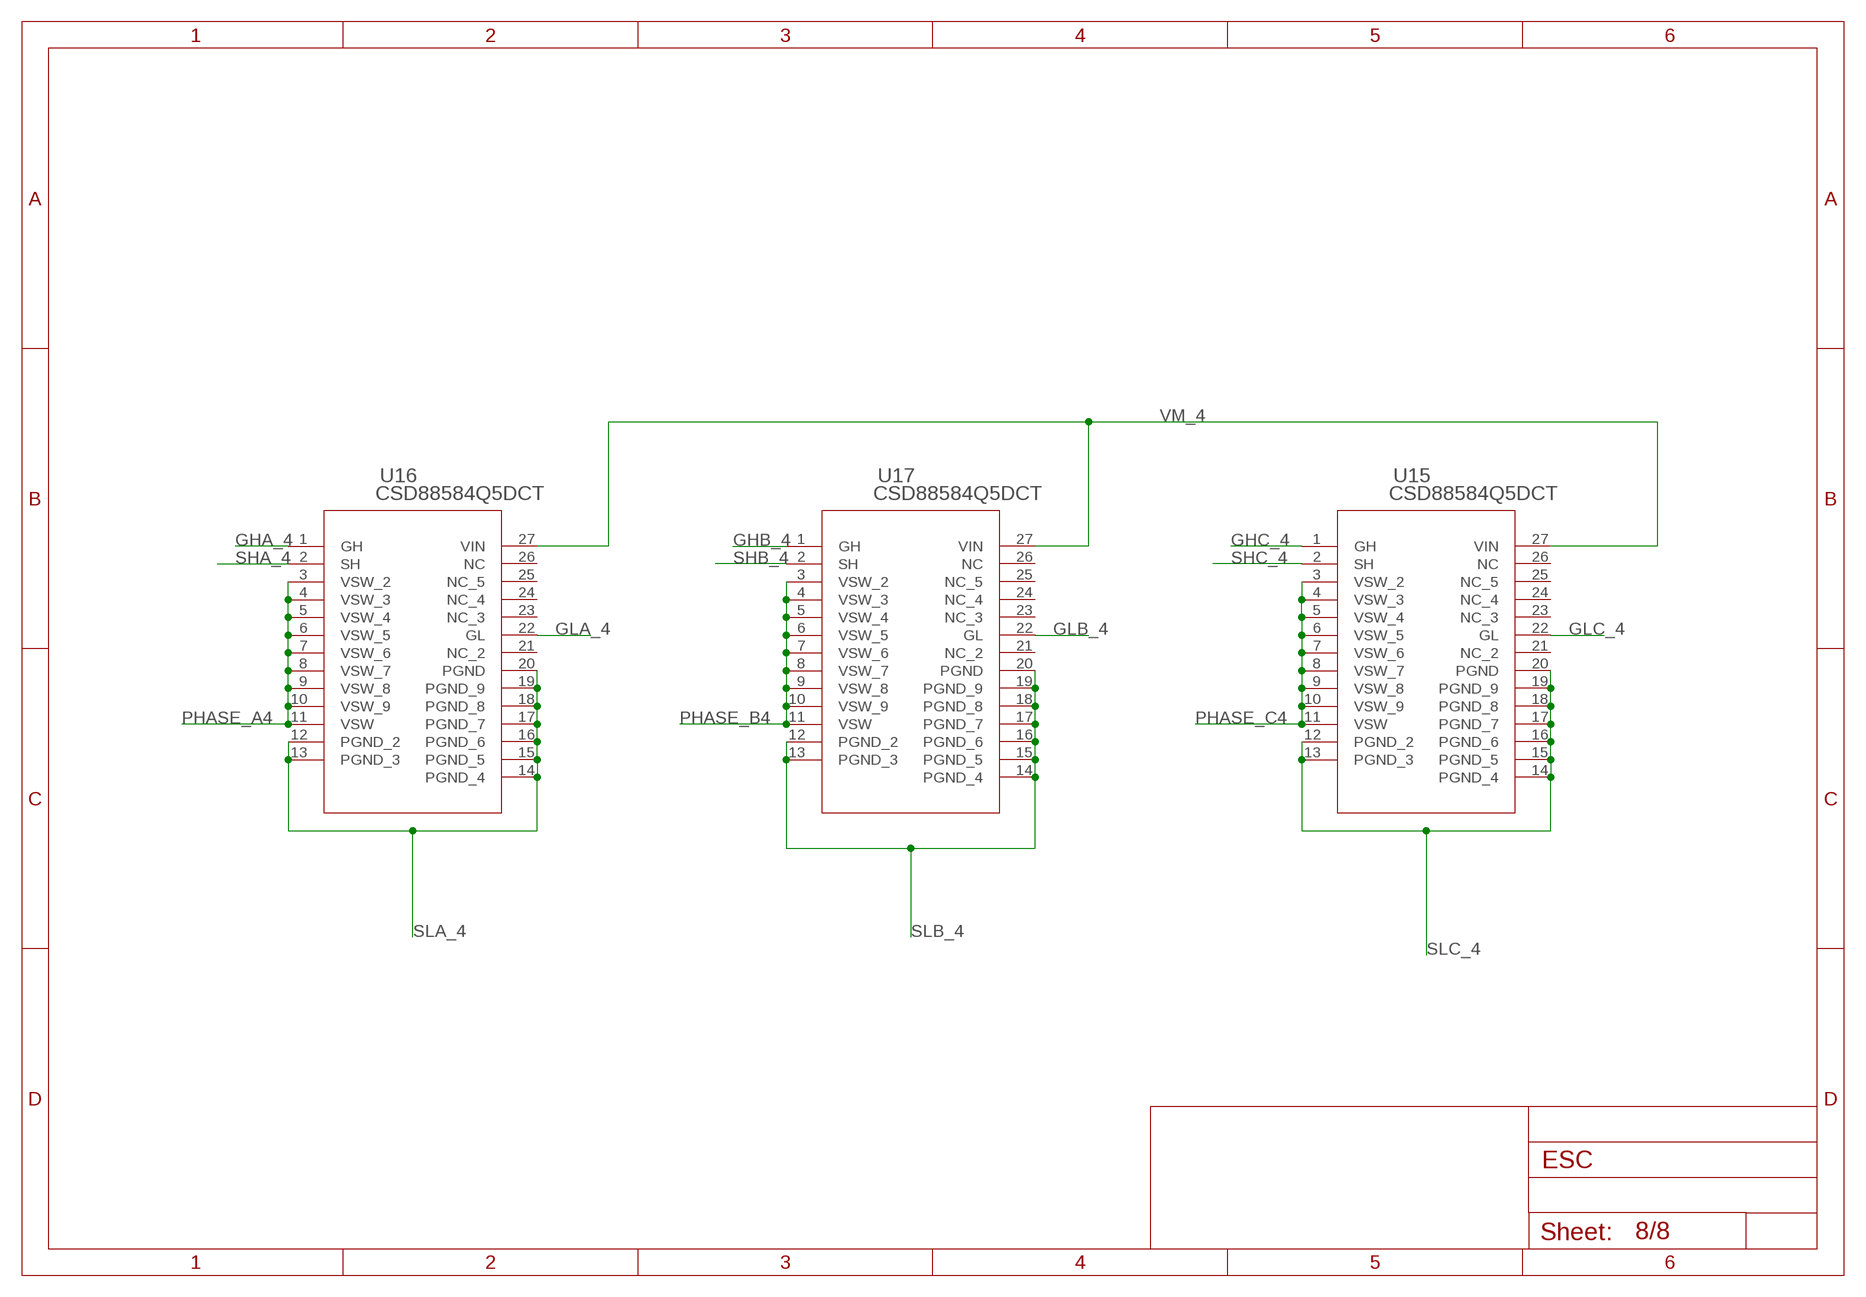
[diagram p11: schematic, sheet 8, part 2 of 2]

(export (version "E")
  (design (tool "Eeschema 10.0.6"))
  (components
    (comp (ref "C6")
      (value "0.1uF")
      (footprint "eagle-import:0603")
      (libsource (lib "eagle-import") (part "0.1UF-0603-25V-(+80/-20%)"))
    )
    (comp (ref "R6")
      (value "1.5k")
      (footprint "eagle-import:0603")
      (libsource (lib "eagle-import") (part "1.5KOHM-0603-1/10W-1%"))
    )
    (comp (ref "U14")
      (value "SN74CBTLV3257PWR")
      (footprint "eagle-import:SN74CBTLV3257PWR")
      (libsource (lib "eagle-import") (part "SN74CBTLV3257PWR"))
    )
    (comp (ref "C1")
      (value "2.2uF")
      (footprint "eagle-import:0603")
      (libsource (lib "eagle-import") (part "2.2UF-0603-10V-20%"))
    )
    (comp (ref "C2")
      (value "4.7uF")
      (footprint "eagle-import:0603")
      (libsource (lib "eagle-import") (part "4.7UF0603"))
    )
    (comp (ref "C3")
      (value "2.2uF")
      (footprint "eagle-import:0603")
      (libsource (lib "eagle-import") (part "2.2UF-0603-10V-20%"))
    )
    (comp (ref "C4")
      (value "4.7uF")
      (footprint "eagle-import:0603")
      (libsource (lib "eagle-import") (part "4.7UF0603"))
    )
    (comp (ref "C5")
      (value "4.7uF")
      (footprint "eagle-import:0603")
      (libsource (lib "eagle-import") (part "4.7UF0603"))
    )
    (comp (ref "C10")
      (value "4.7uF")
      (footprint "eagle-import:0603")
      (libsource (lib "eagle-import") (part "4.7UF0603"))
    )
    (comp (ref "C11")
      (value "4.7uF")
      (footprint "eagle-import:0603")
      (libsource (lib "eagle-import") (part "4.7UF0603"))
    )
    (comp (ref "C12")
      (value "4.7uF")
      (footprint "eagle-import:0603")
      (libsource (lib "eagle-import") (part "4.7UF0603"))
    )
    (comp (ref "C16")
      (value "4.7uF")
      (footprint "eagle-import:0603")
      (libsource (lib "eagle-import") (part "4.7UF0603"))
    )
    (comp (ref "C32")
      (value "4.7uF")
      (footprint "eagle-import:0603")
      (libsource (lib "eagle-import") (part "4.7UF0603"))
    )
    (comp (ref "C33")
      (value "4.7uF")
      (footprint "eagle-import:0603")
      (libsource (lib "eagle-import") (part "4.7UF0603"))
    )
    (comp (ref "C34")
      (value "4.7uF")
      (footprint "eagle-import:0603")
      (libsource (lib "eagle-import") (part "4.7UF0603"))
    )
    (comp (ref "C35")
      (value "4.7uF")
      (footprint "eagle-import:0603")
      (libsource (lib "eagle-import") (part "4.7UF0603"))
    )
    (comp (ref "C38")
      (value "4.7uF")
      (footprint "eagle-import:0603")
      (libsource (lib "eagle-import") (part "4.7UF0603"))
    )
    (comp (ref "C39")
      (value "4.7uF")
      (footprint "eagle-import:0603")
      (libsource (lib "eagle-import") (part "4.7UF0603"))
    )
    (comp (ref "C40")
      (value "4.7uF")
      (footprint "eagle-import:0603")
      (libsource (lib "eagle-import") (part "4.7UF0603"))
    )
    (comp (ref "C41")
      (value "4.7uF")
      (footprint "eagle-import:0603")
      (libsource (lib "eagle-import") (part "4.7UF0603"))
    )
    (comp (ref "GREEN_LED")
      (value "TLMS1100-GS08")
      (footprint "eagle-import:LED_VISHAY_TLMX1100")
      (fields (field (name "MANUFACTURER_PART_NUMBER") "TLMS1100GS08"))
      (libsource (lib "eagle-import") (part "TLMS1100-GS08"))
    )
    (comp (ref "R1")
      (value "1k")
      (footprint "eagle-import:0603")
      (libsource (lib "eagle-import") (part "1KOHM-0603-1/10W-1%"))
    )
    (comp (ref "R2")
      (value "1k")
      (footprint "eagle-import:0603")
      (libsource (lib "eagle-import") (part "1KOHM-0603-1/10W-1%"))
    )
    (comp (ref "R3")
      (value "1k")
      (footprint "eagle-import:0603")
      (libsource (lib "eagle-import") (part "1KOHM-0603-1/10W-1%"))
    )
    (comp (ref "R4")
      (value "1k")
      (footprint "eagle-import:0603")
      (libsource (lib "eagle-import") (part "1KOHM-0603-1/10W-1%"))
    )
    (comp (ref "R5")
      (value "1k")
      (footprint "eagle-import:0603")
      (libsource (lib "eagle-import") (part "1KOHM-0603-1/10W-1%"))
    )
    (comp (ref "RED_LED")
      (value "TLMS1100-GS08")
      (footprint "eagle-import:LED_VISHAY_TLMX1100")
      (fields (field (name "MANUFACTURER_PART_NUMBER") "TLMS1100GS08"))
      (libsource (lib "eagle-import") (part "TLMS1100-GS08"))
    )
    (comp (ref "RESET1")
      (value "SWITCH")
      (footprint "eagle-import:SW_2512")
      (libsource (lib "eagle-import") (part "SWITCH"))
    )
    (comp (ref "U1")
      (value "STM32F405RGT6")
      (footprint "eagle-import:LQFP-64")
      (libsource (lib "eagle-import") (part "STM32F405RGT6"))
    )
    (comp (ref "Y1")
      (value "ECS-80-S-4X")
      (footprint "eagle-import:XTAL_ECS-80-S-4X")
      (fields (field (name "DIGI-KEY_PART_NUMBER") "X1057-ND") (field (name "MF") "ECS International"))
      (libsource (lib "eagle-import") (part "ECS-80-S-4X"))
    )
    (comp (ref "C13")
      (value "47nF")
      (footprint "eagle-import:0603")
      (libsource (lib "eagle-import") (part "47NF-0603-25V-5%"))
    )
    (comp (ref "C14")
      (value "1.0uF")
      (footprint "eagle-import:0603")
      (libsource (lib "eagle-import") (part "1.0UF-0603-16V-10%"))
    )
    (comp (ref "C15")
      (value "0.1uF")
      (footprint "eagle-import:0603")
      (libsource (lib "eagle-import") (part "0.1UF-0603-25V-(+80/-20%)"))
    )
    (comp (ref "C17")
      (value "1.0uF")
      (footprint "eagle-import:0603")
      (libsource (lib "eagle-import") (part "1.0UF-0603-16V-10%"))
    )
    (comp (ref "R7")
      (value "47k")
      (footprint "eagle-import:R0603")
      (libsource (lib "eagle-import") (part "R-US_R0603"))
    )
    (comp (ref "R8")
      (value "R-US_R0603")
      (footprint "eagle-import:R0603")
      (libsource (lib "eagle-import") (part "R-US_R0603"))
    )
    (comp (ref "R9")
      (value "R-US_R0603")
      (footprint "eagle-import:R0603")
      (libsource (lib "eagle-import") (part "R-US_R0603"))
    )
    (comp (ref "R10")
      (value "R-US_R0603")
      (footprint "eagle-import:R0603")
      (libsource (lib "eagle-import") (part "R-US_R0603"))
    )
    (comp (ref "R11")
      (value "R-US_R0603")
      (footprint "eagle-import:R0603")
      (libsource (lib "eagle-import") (part "R-US_R0603"))
    )
    (comp (ref "U$2")
      (value "DRV8320H")
      (footprint "eagle-import:QFN-32-5X5MM")
      (libsource (lib "eagle-import") (part "DRV8320H"))
    )
    (comp (ref "U2")
      (value "CSD88584Q5DCT")
      (footprint "eagle-import:DMM0022A")
      (libsource (lib "eagle-import") (part "CSD88584Q5DCT"))
    )
    (comp (ref "U3")
      (value "CSD88584Q5DCT")
      (footprint "eagle-import:DMM0022A")
      (libsource (lib "eagle-import") (part "CSD88584Q5DCT"))
    )
    (comp (ref "U4")
      (value "CSD88584Q5DCT")
      (footprint "eagle-import:DMM0022A")
      (libsource (lib "eagle-import") (part "CSD88584Q5DCT"))
    )
    (comp (ref "C27")
      (value "47nF")
      (footprint "eagle-import:0603")
      (libsource (lib "eagle-import") (part "47NF-0603-25V-5%"))
    )
    (comp (ref "C28")
      (value "1.0uF")
      (footprint "eagle-import:0603")
      (libsource (lib "eagle-import") (part "1.0UF-0603-16V-10%"))
    )
    (comp (ref "C29")
      (value "0.1uF")
      (footprint "eagle-import:0603")
      (libsource (lib "eagle-import") (part "0.1UF-0603-25V-(+80/-20%)"))
    )
    (comp (ref "C36")
      (value "1.0uF")
      (footprint "eagle-import:0603")
      (libsource (lib "eagle-import") (part "1.0UF-0603-16V-10%"))
    )
    (comp (ref "R27")
      (value "47k")
      (footprint "eagle-import:R0603")
      (libsource (lib "eagle-import") (part "R-US_R0603"))
    )
    (comp (ref "R30")
      (value "R-US_R0603")
      (footprint "eagle-import:R0603")
      (libsource (lib "eagle-import") (part "R-US_R0603"))
    )
    (comp (ref "R31")
      (value "R-US_R0603")
      (footprint "eagle-import:R0603")
      (libsource (lib "eagle-import") (part "R-US_R0603"))
    )
    (comp (ref "R32")
      (value "R-US_R0603")
      (footprint "eagle-import:R0603")
      (libsource (lib "eagle-import") (part "R-US_R0603"))
    )
    (comp (ref "R33")
      (value "R-US_R0603")
      (footprint "eagle-import:R0603")
      (libsource (lib "eagle-import") (part "R-US_R0603"))
    )
    (comp (ref "U$7")
      (value "DRV8320H")
      (footprint "eagle-import:QFN-32-5X5MM")
      (libsource (lib "eagle-import") (part "DRV8320H"))
    )
    (comp (ref "U15")
      (value "CSD88584Q5DCT")
      (footprint "eagle-import:DMM0022A")
      (libsource (lib "eagle-import") (part "CSD88584Q5DCT"))
    )
    (comp (ref "U16")
      (value "CSD88584Q5DCT")
      (footprint "eagle-import:DMM0022A")
      (libsource (lib "eagle-import") (part "CSD88584Q5DCT"))
    )
    (comp (ref "U17")
      (value "CSD88584Q5DCT")
      (footprint "eagle-import:DMM0022A")
      (libsource (lib "eagle-import") (part "CSD88584Q5DCT"))
    )
    (comp (ref "C23")
      (value "47nF")
      (footprint "eagle-import:0603")
      (libsource (lib "eagle-import") (part "47NF-0603-25V-5%"))
    )
    (comp (ref "C24")
      (value "1.0uF")
      (footprint "eagle-import:0603")
      (libsource (lib "eagle-import") (part "1.0UF-0603-16V-10%"))
    )
    (comp (ref "C25")
      (value "0.1uF")
      (footprint "eagle-import:0603")
      (libsource (lib "eagle-import") (part "0.1UF-0603-25V-(+80/-20%)"))
    )
    (comp (ref "C26")
      (value "1.0uF")
      (footprint "eagle-import:0603")
      (libsource (lib "eagle-import") (part "1.0UF-0603-16V-10%"))
    )
    (comp (ref "R22")
      (value "47k")
      (footprint "eagle-import:R0603")
      (libsource (lib "eagle-import") (part "R-US_R0603"))
    )
    (comp (ref "R23")
      (value "R-US_R0603")
      (footprint "eagle-import:R0603")
      (libsource (lib "eagle-import") (part "R-US_R0603"))
    )
    (comp (ref "R24")
      (value "R-US_R0603")
      (footprint "eagle-import:R0603")
      (libsource (lib "eagle-import") (part "R-US_R0603"))
    )
    (comp (ref "R25")
      (value "R-US_R0603")
      (footprint "eagle-import:R0603")
      (libsource (lib "eagle-import") (part "R-US_R0603"))
    )
    (comp (ref "R26")
      (value "R-US_R0603")
      (footprint "eagle-import:R0603")
      (libsource (lib "eagle-import") (part "R-US_R0603"))
    )
    (comp (ref "U$4")
      (value "DRV8320H")
      (footprint "eagle-import:QFN-32-5X5MM")
      (libsource (lib "eagle-import") (part "DRV8320H"))
    )
    (comp (ref "U11")
      (value "CSD88584Q5DCT")
      (footprint "eagle-import:DMM0022A")
      (libsource (lib "eagle-import") (part "CSD88584Q5DCT"))
    )
    (comp (ref "U12")
      (value "CSD88584Q5DCT")
      (footprint "eagle-import:DMM0022A")
      (libsource (lib "eagle-import") (part "CSD88584Q5DCT"))
    )
    (comp (ref "U13")
      (value "CSD88584Q5DCT")
      (footprint "eagle-import:DMM0022A")
      (libsource (lib "eagle-import") (part "CSD88584Q5DCT"))
    )
    (comp (ref "C19")
      (value "47nF")
      (footprint "eagle-import:0603")
      (libsource (lib "eagle-import") (part "47NF-0603-25V-5%"))
    )
    (comp (ref "C20")
      (value "1.0uF")
      (footprint "eagle-import:0603")
      (libsource (lib "eagle-import") (part "1.0UF-0603-16V-10%"))
    )
    (comp (ref "C21")
      (value "0.1uF")
      (footprint "eagle-import:0603")
      (libsource (lib "eagle-import") (part "0.1UF-0603-25V-(+80/-20%)"))
    )
    (comp (ref "C22")
      (value "1.0uF")
      (footprint "eagle-import:0603")
      (libsource (lib "eagle-import") (part "1.0UF-0603-16V-10%"))
    )
    (comp (ref "R17")
      (value "47k")
      (footprint "eagle-import:R0603")
      (libsource (lib "eagle-import") (part "R-US_R0603"))
    )
    (comp (ref "R18")
      (value "R-US_R0603")
      (footprint "eagle-import:R0603")
      (libsource (lib "eagle-import") (part "R-US_R0603"))
    )
    (comp (ref "R19")
      (value "R-US_R0603")
      (footprint "eagle-import:R0603")
      (libsource (lib "eagle-import") (part "R-US_R0603"))
    )
    (comp (ref "R20")
      (value "R-US_R0603")
      (footprint "eagle-import:R0603")
      (libsource (lib "eagle-import") (part "R-US_R0603"))
    )
    (comp (ref "R21")
      (value "R-US_R0603")
      (footprint "eagle-import:R0603")
      (libsource (lib "eagle-import") (part "R-US_R0603"))
    )
    (comp (ref "U$3")
      (value "DRV8320H")
      (footprint "eagle-import:QFN-32-5X5MM")
      (libsource (lib "eagle-import") (part "DRV8320H"))
    )
    (comp (ref "U8")
      (value "CSD88584Q5DCT")
      (footprint "eagle-import:DMM0022A")
      (libsource (lib "eagle-import") (part "CSD88584Q5DCT"))
    )
    (comp (ref "U9")
      (value "CSD88584Q5DCT")
      (footprint "eagle-import:DMM0022A")
      (libsource (lib "eagle-import") (part "CSD88584Q5DCT"))
    )
    (comp (ref "U10")
      (value "CSD88584Q5DCT")
      (footprint "eagle-import:DMM0022A")
      (libsource (lib "eagle-import") (part "CSD88584Q5DCT"))
    )
    (comp (ref "C30")
      (value "4.7uF")
      (footprint "eagle-import:0603")
      (libsource (lib "eagle-import") (part "4.7UF0603"))
    )
    (comp (ref "C31")
      (value "0.1uF")
      (footprint "eagle-import:0603")
      (libsource (lib "eagle-import") (part "0.1UF-0603-25V-(+80/-20%)"))
    )
    (comp (ref "R28")
      (value "60")
      (footprint "eagle-import:0603")
      (libsource (lib "eagle-import") (part "1KOHM-0603-1/10W-1%"))
    )
    (comp (ref "R29")
      (value "60")
      (footprint "eagle-import:0603")
      (libsource (lib "eagle-import") (part "1KOHM-0603-1/10W-1%"))
    )
    (comp (ref "U$6")
      (value "TCAN337D")
      (footprint "eagle-import:TCAN337D")
      (libsource (lib "eagle-import") (part "TCAN337D"))
    )
    (comp (ref "J1")
      (value "1755529")
      (footprint "eagle-import:CONN_1755529")
      (libsource (lib "eagle-import") (part "1755529"))
    )
    (comp (ref "J2")
      (value "1755529")
      (footprint "eagle-import:CONN_1755529")
      (libsource (lib "eagle-import") (part "1755529"))
    )
    (comp (ref "J3")
      (value "1755529")
      (footprint "eagle-import:CONN_1755529")
      (libsource (lib "eagle-import") (part "1755529"))
    )
    (comp (ref "J4")
      (value "1755529")
      (footprint "eagle-import:CONN_1755529")
      (libsource (lib "eagle-import") (part "1755529"))
    )
    (comp (ref "SV2")
      (value "FE05-1")
      (footprint "eagle-import:FE05-1")
      (libsource (lib "eagle-import") (part "FE05-1"))
    )
    (comp (ref "U$5")
      (value "ESC2BACKPLANE")
      (footprint "eagle-import:ESC2BACKPLANE_WHOLE")
      (libsource (lib "eagle-import") (part "ESC2BACKPLANE"))
    )
  )
  (nets
    (net (code "1") (name "+3V3") (class "Default")
      (node (ref "C12") (pin "1") (pinfunction "1_1") (pintype "passive"))
      (node (ref "C16") (pin "1") (pinfunction "1_1") (pintype "passive"))
      (node (ref "C30") (pin "1") (pinfunction "1_1") (pintype "passive"))
      (node (ref "C32") (pin "1") (pinfunction "1_1") (pintype "passive"))
      (node (ref "C33") (pin "1") (pinfunction "1_1") (pintype "passive"))
      (node (ref "C34") (pin "1") (pinfunction "1_1") (pintype "passive"))
      (node (ref "C35") (pin "1") (pinfunction "1_1") (pintype "passive"))
      (node (ref "C38") (pin "1") (pinfunction "1_1") (pintype "passive"))
      (node (ref "C39") (pin "1") (pinfunction "1_1") (pintype "passive"))
      (node (ref "C4") (pin "1") (pinfunction "1_1") (pintype "passive"))
      (node (ref "C40") (pin "1") (pinfunction "1_1") (pintype "passive"))
      (node (ref "C41") (pin "1") (pinfunction "1_1") (pintype "passive"))
      (node (ref "C5") (pin "1") (pinfunction "1_1") (pintype "passive"))
      (node (ref "C6") (pin "1") (pinfunction "1_1") (pintype "passive"))
      (node (ref "R4") (pin "2") (pinfunction "2_2") (pintype "passive"))
      (node (ref "R6") (pin "2") (pinfunction "2_2") (pintype "passive"))
      (node (ref "SV2") (pin "5") (pinfunction "5_5") (pintype "passive"))
      (node (ref "U$5") (pin "P$G") (pinfunction "P$G_P$G") (pintype "bidirectional"))
      (node (ref "U$5") (pin "P$H") (pinfunction "P$H_P$H") (pintype "bidirectional"))
      (node (ref "U$5") (pin "P$U") (pinfunction "P$U_P$U") (pintype "bidirectional"))
      (node (ref "U$5") (pin "P$V") (pinfunction "P$V_P$V") (pintype "bidirectional"))
      (node (ref "U$6") (pin "VCC") (pinfunction "VCC_VCC") (pintype "bidirectional"))
      (node (ref "U1") (pin "1") (pinfunction "VBAT_1") (pintype "power_in"))
      (node (ref "U1") (pin "13") (pinfunction "VDDA_13") (pintype "power_in"))
      (node (ref "U1") (pin "19") (pinfunction "VDD_4_19") (pintype "power_in"))
      (node (ref "U1") (pin "32") (pinfunction "VDD_1_32") (pintype "power_in"))
      (node (ref "U1") (pin "48") (pinfunction "VDD_2_48") (pintype "power_in"))
      (node (ref "U1") (pin "64") (pinfunction "VDD_3_64") (pintype "power_in"))
      (node (ref "U14") (pin "P$16") (pinfunction "VCC_P$16") (pintype "bidirectional"))
    )
    (net (code "2") (name "+12V") (class "Default")
      (node (ref "U$5") (pin "P$10") (pinfunction "P$10_P$10") (pintype "bidirectional"))
      (node (ref "U$5") (pin "P$11") (pinfunction "P$11_P$11") (pintype "bidirectional"))
      (node (ref "U$5") (pin "P$12") (pinfunction "P$12_P$12") (pintype "bidirectional"))
      (node (ref "U$5") (pin "P$13") (pinfunction "P$13_P$13") (pintype "bidirectional"))
      (node (ref "U$5") (pin "P$23") (pinfunction "P$23_P$23") (pintype "bidirectional"))
      (node (ref "U$5") (pin "P$24") (pinfunction "P$24_P$24") (pintype "bidirectional"))
      (node (ref "U$5") (pin "P$25") (pinfunction "P$25_P$25") (pintype "bidirectional"))
      (node (ref "U$5") (pin "P$26") (pinfunction "P$26_P$26") (pintype "bidirectional"))
      (node (ref "U$5") (pin "P$27") (pinfunction "P$27_P$27") (pintype "bidirectional"))
      (node (ref "U$5") (pin "P$9") (pinfunction "P$9_P$9") (pintype "bidirectional"))
      (node (ref "U$5") (pin "P$A") (pinfunction "P$A_P$A") (pintype "bidirectional"))
      (node (ref "U$5") (pin "P$B") (pinfunction "P$B_P$B") (pintype "bidirectional"))
      (node (ref "U$5") (pin "P$C") (pinfunction "P$C_P$C") (pintype "bidirectional"))
      (node (ref "U$5") (pin "P$D") (pinfunction "P$D_P$D") (pintype "bidirectional"))
      (node (ref "U$5") (pin "P$E") (pinfunction "P$E_P$E") (pintype "bidirectional"))
      (node (ref "U$5") (pin "P$O") (pinfunction "P$O_P$O") (pintype "bidirectional"))
      (node (ref "U$5") (pin "P$P") (pinfunction "P$P_P$P") (pintype "bidirectional"))
      (node (ref "U$5") (pin "P$Q") (pinfunction "P$Q_P$Q") (pintype "bidirectional"))
      (node (ref "U$5") (pin "P$R") (pinfunction "P$R_P$R") (pintype "bidirectional"))
      (node (ref "U$5") (pin "P$S") (pinfunction "P$S_P$S") (pintype "bidirectional"))
    )
    (net (code "3") (name "CAN_H") (class "Default")
      (node (ref "R28") (pin "2") (pinfunction "2_2") (pintype "passive"))
      (node (ref "U$5") (pin "P$6") (pinfunction "P$6_P$6") (pintype "bidirectional"))
      (node (ref "U$6") (pin "CANH") (pinfunction "CANH_CANH") (pintype "bidirectional"))
    )
    (net (code "4") (name "CAN_L") (class "Default")
      (node (ref "R29") (pin "1") (pinfunction "1_1") (pintype "passive"))
      (node (ref "U$5") (pin "P$7") (pinfunction "P$7_P$7") (pintype "bidirectional"))
      (node (ref "U$6") (pin "CANL") (pinfunction "CANL_CANL") (pintype "bidirectional"))
    )
    (net (code "5") (name "CAN_RX") (class "Default")
      (node (ref "U$6") (pin "RXD") (pinfunction "RXD_RXD") (pintype "bidirectional"))
      (node (ref "U1") (pin "61") (pinfunction "PB8_61") (pintype "bidirectional"))
    )
    (net (code "6") (name "CAN_TX") (class "Default")
      (node (ref "U$6") (pin "TXD") (pinfunction "TXD_TXD") (pintype "bidirectional"))
      (node (ref "U1") (pin "62") (pinfunction "PB9_62") (pintype "bidirectional"))
    )
    (net (code "7") (name "DVDD_1") (class "Default")
      (node (ref "C14") (pin "1") (pinfunction "1_1") (pintype "passive"))
      (node (ref "R10") (pin "2") (pinfunction "2_2") (pintype "passive"))
      (node (ref "R8") (pin "2") (pinfunction "2_2") (pintype "passive"))
      (node (ref "U$2") (pin "24") (pinfunction "DVDD_24") (pintype "passive"))
    )
    (net (code "8") (name "DVDD_2") (class "Default")
      (node (ref "C20") (pin "1") (pinfunction "1_1") (pintype "passive"))
      (node (ref "R18") (pin "2") (pinfunction "2_2") (pintype "passive"))
      (node (ref "R20") (pin "2") (pinfunction "2_2") (pintype "passive"))
      (node (ref "U$3") (pin "24") (pinfunction "DVDD_24") (pintype "passive"))
    )
    (net (code "9") (name "DVDD_3") (class "Default")
      (node (ref "C24") (pin "1") (pinfunction "1_1") (pintype "passive"))
      (node (ref "R23") (pin "2") (pinfunction "2_2") (pintype "passive"))
      (node (ref "R25") (pin "2") (pinfunction "2_2") (pintype "passive"))
      (node (ref "U$4") (pin "24") (pinfunction "DVDD_24") (pintype "passive"))
    )
    (net (code "10") (name "DVDD_4") (class "Default")
      (node (ref "C28") (pin "1") (pinfunction "1_1") (pintype "passive"))
      (node (ref "R30") (pin "2") (pinfunction "2_2") (pintype "passive"))
      (node (ref "R32") (pin "2") (pinfunction "2_2") (pintype "passive"))
      (node (ref "U$7") (pin "24") (pinfunction "DVDD_24") (pintype "passive"))
    )
    (net (code "11") (name "EN_1") (class "Default")
      (node (ref "U$2") (pin "22") (pinfunction "ENABLE_22") (pintype "passive"))
      (node (ref "U1") (pin "37") (pinfunction "PC6_37") (pintype "bidirectional"))
    )
    (net (code "12") (name "EN_2") (class "Default")
      (node (ref "U$3") (pin "22") (pinfunction "ENABLE_22") (pintype "passive"))
      (node (ref "U1") (pin "43") (pinfunction "PA10_43") (pintype "bidirectional"))
    )
    (net (code "13") (name "EN_3") (class "Default")
      (node (ref "U$4") (pin "22") (pinfunction "ENABLE_22") (pintype "passive"))
      (node (ref "U1") (pin "55") (pinfunction "PB3_55") (pintype "bidirectional"))
    )
    (net (code "14") (name "EN_4") (class "Default")
      (node (ref "U$7") (pin "22") (pinfunction "ENABLE_22") (pintype "passive"))
      (node (ref "U1") (pin "27") (pinfunction "PB1_27") (pintype "bidirectional"))
    )
    (net (code "15") (name "FAULT_1") (class "Default")
      (node (ref "U$2") (pin "17") (pinfunction "FAULT_N_17") (pintype "passive"))
      (node (ref "U1") (pin "38") (pinfunction "PC7_38") (pintype "bidirectional"))
    )
    (net (code "16") (name "FAULT_2") (class "Default")
      (node (ref "U$3") (pin "17") (pinfunction "FAULT_N_17") (pintype "passive"))
      (node (ref "U1") (pin "44") (pinfunction "PA11_44") (pintype "bidirectional"))
    )
    (net (code "17") (name "FAULT_3") (class "Default")
      (node (ref "U$4") (pin "17") (pinfunction "FAULT_N_17") (pintype "passive"))
      (node (ref "U1") (pin "54") (pinfunction "PD2_54") (pintype "bidirectional"))
    )
    (net (code "18") (name "FAULT_4") (class "Default")
      (node (ref "U$7") (pin "17") (pinfunction "FAULT_N_17") (pintype "passive"))
      (node (ref "U1") (pin "28") (pinfunction "PB2_28") (pintype "bidirectional"))
    )
    (net (code "19") (name "GHA_1") (class "Default")
      (node (ref "U$2") (pin "5") (pinfunction "GHA_5") (pintype "passive"))
      (node (ref "U3") (pin "1") (pinfunction "GH_1") (pintype "passive"))
    )
    (net (code "20") (name "GHA_2") (class "Default")
      (node (ref "U$3") (pin "5") (pinfunction "GHA_5") (pintype "passive"))
      (node (ref "U9") (pin "1") (pinfunction "GH_1") (pintype "passive"))
    )
    (net (code "21") (name "GHA_3") (class "Default")
      (node (ref "U$4") (pin "5") (pinfunction "GHA_5") (pintype "passive"))
      (node (ref "U12") (pin "1") (pinfunction "GH_1") (pintype "passive"))
    )
    (net (code "22") (name "GHA_4") (class "Default")
      (node (ref "U$7") (pin "5") (pinfunction "GHA_5") (pintype "passive"))
      (node (ref "U16") (pin "1") (pinfunction "GH_1") (pintype "passive"))
    )
    (net (code "23") (name "GHB_1") (class "Default")
      (node (ref "U$2") (pin "12") (pinfunction "GHB_12") (pintype "passive"))
      (node (ref "U4") (pin "1") (pinfunction "GH_1") (pintype "passive"))
    )
    (net (code "24") (name "GHB_2") (class "Default")
      (node (ref "U$3") (pin "12") (pinfunction "GHB_12") (pintype "passive"))
      (node (ref "U10") (pin "1") (pinfunction "GH_1") (pintype "passive"))
    )
    (net (code "25") (name "GHB_3") (class "Default")
      (node (ref "U$4") (pin "12") (pinfunction "GHB_12") (pintype "passive"))
      (node (ref "U13") (pin "1") (pinfunction "GH_1") (pintype "passive"))
    )
    (net (code "26") (name "GHB_4") (class "Default")
      (node (ref "U$7") (pin "12") (pinfunction "GHB_12") (pintype "passive"))
      (node (ref "U17") (pin "1") (pinfunction "GH_1") (pintype "passive"))
    )
    (net (code "27") (name "GHC_1") (class "Default")
      (node (ref "U$2") (pin "13") (pinfunction "GHC_13") (pintype "passive"))
      (node (ref "U2") (pin "1") (pinfunction "GH_1") (pintype "passive"))
    )
    (net (code "28") (name "GHC_2") (class "Default")
      (node (ref "U$3") (pin "13") (pinfunction "GHC_13") (pintype "passive"))
      (node (ref "U8") (pin "1") (pinfunction "GH_1") (pintype "passive"))
    )
    (net (code "29") (name "GHC_3") (class "Default")
      (node (ref "U$4") (pin "13") (pinfunction "GHC_13") (pintype "passive"))
      (node (ref "U11") (pin "1") (pinfunction "GH_1") (pintype "passive"))
    )
    (net (code "30") (name "GHC_4") (class "Default")
      (node (ref "U$7") (pin "13") (pinfunction "GHC_13") (pintype "passive"))
      (node (ref "U15") (pin "1") (pinfunction "GH_1") (pintype "passive"))
    )
    (net (code "31") (name "GLA_1") (class "Default")
      (node (ref "U$2") (pin "7") (pinfunction "GLA_7") (pintype "passive"))
      (node (ref "U3") (pin "22") (pinfunction "GL_22") (pintype "passive"))
    )
    (net (code "32") (name "GLA_2") (class "Default")
      (node (ref "U$3") (pin "7") (pinfunction "GLA_7") (pintype "passive"))
      (node (ref "U9") (pin "22") (pinfunction "GL_22") (pintype "passive"))
    )
    (net (code "33") (name "GLA_3") (class "Default")
      (node (ref "U$4") (pin "7") (pinfunction "GLA_7") (pintype "passive"))
      (node (ref "U12") (pin "22") (pinfunction "GL_22") (pintype "passive"))
    )
    (net (code "34") (name "GLA_4") (class "Default")
      (node (ref "U$7") (pin "7") (pinfunction "GLA_7") (pintype "passive"))
      (node (ref "U16") (pin "22") (pinfunction "GL_22") (pintype "passive"))
    )
    (net (code "35") (name "GLB_1") (class "Default")
      (node (ref "U$2") (pin "10") (pinfunction "GLB_10") (pintype "passive"))
      (node (ref "U4") (pin "22") (pinfunction "GL_22") (pintype "passive"))
    )
    (net (code "36") (name "GLB_2") (class "Default")
      (node (ref "U$3") (pin "10") (pinfunction "GLB_10") (pintype "passive"))
      (node (ref "U10") (pin "22") (pinfunction "GL_22") (pintype "passive"))
    )
    (net (code "37") (name "GLB_3") (class "Default")
      (node (ref "U$4") (pin "10") (pinfunction "GLB_10") (pintype "passive"))
      (node (ref "U13") (pin "22") (pinfunction "GL_22") (pintype "passive"))
    )
    (net (code "38") (name "GLB_4") (class "Default")
      (node (ref "U$7") (pin "10") (pinfunction "GLB_10") (pintype "passive"))
      (node (ref "U17") (pin "22") (pinfunction "GL_22") (pintype "passive"))
    )
    (net (code "39") (name "GLC_1") (class "Default")
      (node (ref "U$2") (pin "15") (pinfunction "GLC_15") (pintype "passive"))
      (node (ref "U2") (pin "22") (pinfunction "GL_22") (pintype "passive"))
    )
    (net (code "40") (name "GLC_2") (class "Default")
      (node (ref "U$3") (pin "15") (pinfunction "GLC_15") (pintype "passive"))
      (node (ref "U8") (pin "22") (pinfunction "GL_22") (pintype "passive"))
    )
    (net (code "41") (name "GLC_3") (class "Default")
      (node (ref "U$4") (pin "15") (pinfunction "GLC_15") (pintype "passive"))
      (node (ref "U11") (pin "22") (pinfunction "GL_22") (pintype "passive"))
    )
    (net (code "42") (name "GLC_4") (class "Default")
      (node (ref "U$7") (pin "15") (pinfunction "GLC_15") (pintype "passive"))
      (node (ref "U15") (pin "22") (pinfunction "GL_22") (pintype "passive"))
    )
    (net (code "43") (name "GND") (class "Default")
      (node (ref "C1") (pin "2") (pinfunction "2_2") (pintype "passive"))
      (node (ref "C10") (pin "2") (pinfunction "2_2") (pintype "passive"))
      (node (ref "C11") (pin "2") (pinfunction "2_2") (pintype "passive"))
      (node (ref "C12") (pin "2") (pinfunction "2_2") (pintype "passive"))
      (node (ref "C14") (pin "2") (pinfunction "2_2") (pintype "passive"))
      (node (ref "C15") (pin "2") (pinfunction "2_2") (pintype "passive"))
      (node (ref "C16") (pin "2") (pinfunction "2_2") (pintype "passive"))
      (node (ref "C2") (pin "2") (pinfunction "2_2") (pintype "passive"))
      (node (ref "C20") (pin "2") (pinfunction "2_2") (pintype "passive"))
      (node (ref "C21") (pin "2") (pinfunction "2_2") (pintype "passive"))
      (node (ref "C24") (pin "2") (pinfunction "2_2") (pintype "passive"))
      (node (ref "C25") (pin "2") (pinfunction "2_2") (pintype "passive"))
      (node (ref "C28") (pin "2") (pinfunction "2_2") (pintype "passive"))
      (node (ref "C29") (pin "2") (pinfunction "2_2") (pintype "passive"))
      (node (ref "C3") (pin "2") (pinfunction "2_2") (pintype "passive"))
      (node (ref "C30") (pin "2") (pinfunction "2_2") (pintype "passive"))
      (node (ref "C31") (pin "1") (pinfunction "1_1") (pintype "passive"))
      (node (ref "C32") (pin "2") (pinfunction "2_2") (pintype "passive"))
      (node (ref "C33") (pin "2") (pinfunction "2_2") (pintype "passive"))
      (node (ref "C34") (pin "2") (pinfunction "2_2") (pintype "passive"))
      (node (ref "C35") (pin "2") (pinfunction "2_2") (pintype "passive"))
      (node (ref "C38") (pin "2") (pinfunction "2_2") (pintype "passive"))
      (node (ref "C39") (pin "2") (pinfunction "2_2") (pintype "passive"))
      (node (ref "C4") (pin "2") (pinfunction "2_2") (pintype "passive"))
      (node (ref "C40") (pin "2") (pinfunction "2_2") (pintype "passive"))
      (node (ref "C41") (pin "2") (pinfunction "2_2") (pintype "passive"))
      (node (ref "C5") (pin "2") (pinfunction "2_2") (pintype "passive"))
      (node (ref "C6") (pin "2") (pinfunction "2_2") (pintype "passive"))
      (node (ref "GREEN_LED") (pin "1") (pinfunction "1_1") (pintype "passive"))
      (node (ref "R11") (pin "1") (pinfunction "1_1") (pintype "passive"))
      (node (ref "R17") (pin "1") (pinfunction "1_1") (pintype "passive"))
      (node (ref "R19") (pin "1") (pinfunction "1_1") (pintype "passive"))
      (node (ref "R21") (pin "1") (pinfunction "1_1") (pintype "passive"))
      (node (ref "R22") (pin "1") (pinfunction "1_1") (pintype "passive"))
      (node (ref "R24") (pin "1") (pinfunction "1_1") (pintype "passive"))
      (node (ref "R26") (pin "1") (pinfunction "1_1") (pintype "passive"))
      (node (ref "R27") (pin "1") (pinfunction "1_1") (pintype "passive"))
      (node (ref "R31") (pin "1") (pinfunction "1_1") (pintype "passive"))
      (node (ref "R33") (pin "1") (pinfunction "1_1") (pintype "passive"))
      (node (ref "R7") (pin "1") (pinfunction "1_1") (pintype "passive"))
      (node (ref "R9") (pin "1") (pinfunction "1_1") (pintype "passive"))
      (node (ref "RED_LED") (pin "1") (pinfunction "1_1") (pintype "passive"))
      (node (ref "RESET1") (pin "1") (pinfunction "P$1_1") (pintype "bidirectional"))
      (node (ref "SV2") (pin "3") (pinfunction "3_3") (pintype "passive"))
      (node (ref "U$2") (pin "23") (pinfunction "AGND_23") (pintype "passive"))
      (node (ref "U$2") (pin "31") (pinfunction "PGND_31") (pintype "passive"))
      (node (ref "U$2") (pin "EP") (pinfunction "PAD_EP") (pintype "passive"))
      (node (ref "U$3") (pin "23") (pinfunction "AGND_23") (pintype "passive"))
      (node (ref "U$3") (pin "31") (pinfunction "PGND_31") (pintype "passive"))
      (node (ref "U$3") (pin "EP") (pinfunction "PAD_EP") (pintype "passive"))
      (node (ref "U$4") (pin "23") (pinfunction "AGND_23") (pintype "passive"))
      (node (ref "U$4") (pin "31") (pinfunction "PGND_31") (pintype "passive"))
      (node (ref "U$4") (pin "EP") (pinfunction "PAD_EP") (pintype "passive"))
      (node (ref "U$5") (pin "P$1") (pinfunction "P$1_P$1") (pintype "bidirectional"))
      (node (ref "U$5") (pin "P$15") (pinfunction "P$15_P$15") (pintype "bidirectional"))
      (node (ref "U$5") (pin "P$16") (pinfunction "P$16_P$16") (pintype "bidirectional"))
      (node (ref "U$5") (pin "P$17") (pinfunction "P$17_P$17") (pintype "bidirectional"))
      (node (ref "U$5") (pin "P$18") (pinfunction "P$18_P$18") (pintype "bidirectional"))
      (node (ref "U$5") (pin "P$2") (pinfunction "P$2_P$2") (pintype "bidirectional"))
      (node (ref "U$5") (pin "P$3") (pinfunction "P$3_P$3") (pintype "bidirectional"))
      (node (ref "U$5") (pin "P$4") (pinfunction "P$4_P$4") (pintype "bidirectional"))
      (node (ref "U$5") (pin "P$AA") (pinfunction "P$AA_P$AA") (pintype "bidirectional"))
      (node (ref "U$5") (pin "P$BB") (pinfunction "P$BB_P$BB") (pintype "bidirectional"))
      (node (ref "U$5") (pin "P$J") (pinfunction "P$J_P$J") (pintype "bidirectional"))
      (node (ref "U$5") (pin "P$K") (pinfunction "P$K_P$K") (pintype "bidirectional"))
      (node (ref "U$5") (pin "P$L") (pinfunction "P$L_P$L") (pintype "bidirectional"))
      (node (ref "U$5") (pin "P$M") (pinfunction "P$M_P$M") (pintype "bidirectional"))
      (node (ref "U$5") (pin "P$N") (pinfunction "P$N_P$N") (pintype "bidirectional"))
      (node (ref "U$5") (pin "P$X") (pinfunction "P$X_P$X") (pintype "bidirectional"))
      (node (ref "U$5") (pin "P$Y") (pinfunction "P$Y_P$Y") (pintype "bidirectional"))
      (node (ref "U$5") (pin "P$Z") (pinfunction "P$Z_P$Z") (pintype "bidirectional"))
      (node (ref "U$6") (pin "GND") (pinfunction "GND_GND") (pintype "bidirectional"))
      (node (ref "U$7") (pin "23") (pinfunction "AGND_23") (pintype "passive"))
      (node (ref "U$7") (pin "31") (pinfunction "PGND_31") (pintype "passive"))
      (node (ref "U$7") (pin "EP") (pinfunction "PAD_EP") (pintype "passive"))
      (node (ref "U1") (pin "12") (pinfunction "VSSA_12") (pintype "power_in"))
      (node (ref "U1") (pin "18") (pinfunction "VSS_4_18") (pintype "power_in"))
      (node (ref "U1") (pin "60") (pinfunction "BOOT0_60") (pintype "input"))
      (node (ref "U1") (pin "63") (pinfunction "VSS__63") (pintype "power_in"))
      (node (ref "U14") (pin "P$8") (pinfunction "GND_P$8") (pintype "bidirectional"))
    )
    (net (code "44") (name "INHA_1") (class "Default")
      (node (ref "U$2") (pin "25") (pinfunction "INHA_25") (pintype "passive"))
      (node (ref "U1") (pin "36") (pinfunction "PB15_36") (pintype "bidirectional"))
    )
    (net (code "45") (name "INHA_2") (class "Default")
      (node (ref "U$3") (pin "25") (pinfunction "INHA_25") (pintype "passive"))
      (node (ref "U1") (pin "42") (pinfunction "PA9_42") (pintype "bidirectional"))
    )
    (net (code "46") (name "INHA_3") (class "Default")
      (node (ref "U$4") (pin "25") (pinfunction "INHA_25") (pintype "passive"))
      (node (ref "U1") (pin "56") (pinfunction "PB4_56") (pintype "bidirectional"))
    )
    (net (code "47") (name "INHA_4") (class "Default")
      (node (ref "U$7") (pin "25") (pinfunction "INHA_25") (pintype "passive"))
      (node (ref "U1") (pin "50") (pinfunction "PA15_50") (pintype "bidirectional"))
    )
    (net (code "48") (name "INHB_1") (class "Default")
      (node (ref "U$2") (pin "27") (pinfunction "INHB_27") (pintype "passive"))
      (node (ref "U1") (pin "35") (pinfunction "PB14_35") (pintype "bidirectional"))
    )
    (net (code "49") (name "INHB_2") (class "Default")
      (node (ref "U$3") (pin "27") (pinfunction "INHB_27") (pintype "passive"))
      (node (ref "U1") (pin "41") (pinfunction "PA8_41") (pintype "bidirectional"))
    )
    (net (code "50") (name "INHB_3") (class "Default")
      (node (ref "U$4") (pin "27") (pinfunction "INHB_27") (pintype "passive"))
      (node (ref "U1") (pin "57") (pinfunction "PB5_57") (pintype "bidirectional"))
    )
    (net (code "51") (name "INHB_4") (class "Default")
      (node (ref "U$7") (pin "27") (pinfunction "INHB_27") (pintype "passive"))
      (node (ref "U1") (pin "51") (pinfunction "PC10_51") (pintype "bidirectional"))
    )
    (net (code "52") (name "INHC_1") (class "Default")
      (node (ref "U$2") (pin "29") (pinfunction "INHC_29") (pintype "passive"))
      (node (ref "U1") (pin "34") (pinfunction "PB13_34") (pintype "bidirectional"))
    )
    (net (code "53") (name "INHC_2") (class "Default")
      (node (ref "U$3") (pin "29") (pinfunction "INHC_29") (pintype "passive"))
      (node (ref "U1") (pin "40") (pinfunction "PC9_40") (pintype "bidirectional"))
    )
    (net (code "54") (name "INHC_3") (class "Default")
      (node (ref "U$4") (pin "29") (pinfunction "INHC_29") (pintype "passive"))
      (node (ref "U1") (pin "59") (pinfunction "PB7_59") (pintype "bidirectional"))
    )
    (net (code "55") (name "INHC_4") (class "Default")
      (node (ref "U$7") (pin "29") (pinfunction "INHC_29") (pintype "passive"))
      (node (ref "U1") (pin "53") (pinfunction "PC12_53") (pintype "bidirectional"))
    )
    (net (code "56") (name "INL_1") (class "Default")
      (node (ref "U$2") (pin "26") (pinfunction "INLA_26") (pintype "passive"))
      (node (ref "U$2") (pin "28") (pinfunction "INLB_28") (pintype "passive"))
      (node (ref "U$2") (pin "30") (pinfunction "INLC_30") (pintype "passive"))
      (node (ref "U1") (pin "33") (pinfunction "PB12_33") (pintype "bidirectional"))
    )
    (net (code "57") (name "INL_2") (class "Default")
      (node (ref "U$3") (pin "26") (pinfunction "INLA_26") (pintype "passive"))
      (node (ref "U$3") (pin "28") (pinfunction "INLB_28") (pintype "passive"))
      (node (ref "U$3") (pin "30") (pinfunction "INLC_30") (pintype "passive"))
      (node (ref "U1") (pin "39") (pinfunction "PC8_39") (pintype "bidirectional"))
    )
    (net (code "58") (name "INL_3") (class "Default")
      (node (ref "U$4") (pin "26") (pinfunction "INLA_26") (pintype "passive"))
      (node (ref "U$4") (pin "28") (pinfunction "INLB_28") (pintype "passive"))
      (node (ref "U$4") (pin "30") (pinfunction "INLC_30") (pintype "passive"))
      (node (ref "U1") (pin "58") (pinfunction "PB6_58") (pintype "bidirectional"))
    )
    (net (code "59") (name "INL_4") (class "Default")
      (node (ref "U$7") (pin "26") (pinfunction "INLA_26") (pintype "passive"))
      (node (ref "U$7") (pin "28") (pinfunction "INLB_28") (pintype "passive"))
      (node (ref "U$7") (pin "30") (pinfunction "INLC_30") (pintype "passive"))
      (node (ref "U1") (pin "52") (pinfunction "PC11_52") (pintype "bidirectional"))
    )
    (net (code "60") (name "NRST") (class "Default")
      (node (ref "C10") (pin "1") (pinfunction "1_1") (pintype "passive"))
      (node (ref "R4") (pin "1") (pinfunction "1_1") (pintype "passive"))
      (node (ref "RESET1") (pin "2") (pinfunction "P$2_2") (pintype "bidirectional"))
      (node (ref "SV2") (pin "1") (pinfunction "1_1") (pintype "passive"))
      (node (ref "U1") (pin "7") (pinfunction "NRST_7") (pintype "bidirectional"))
      (node (ref "U14") (pin "P$11") (pinfunction "3B1_P$11") (pintype "bidirectional"))
    )
    (net (code "61") (name "NRST_IN") (class "Default")
      (node (ref "U14") (pin "P$9") (pinfunction "3A_P$9") (pintype "bidirectional"))
    )
    (net (code "62") (name "Net-(C2-Pad1)") (class "Default")
      (node (ref "C2") (pin "1") (pinfunction "1_1") (pintype "passive"))
      (node (ref "R5") (pin "1") (pinfunction "1_1") (pintype "passive"))
      (node (ref "Y1") (pin "1") (pinfunction "1_1") (pintype "passive"))
    )
    (net (code "63") (name "Net-(C11-Pad1)") (class "Default")
      (node (ref "C11") (pin "1") (pinfunction "1_1") (pintype "passive"))
      (node (ref "R3") (pin "1") (pinfunction "1_1") (pintype "passive"))
      (node (ref "Y1") (pin "2") (pinfunction "2_2") (pintype "passive"))
    )
    (net (code "64") (name "Net-(C31-Pad2)") (class "Default")
      (node (ref "C31") (pin "2") (pinfunction "2_2") (pintype "passive"))
      (node (ref "R28") (pin "1") (pinfunction "1_1") (pintype "passive"))
      (node (ref "R29") (pin "2") (pinfunction "2_2") (pintype "passive"))
    )
    (net (code "65") (name "Net-(GREEN_LED-Pad2)") (class "Default")
      (node (ref "GREEN_LED") (pin "2") (pinfunction "2_2") (pintype "passive"))
      (node (ref "R1") (pin "1") (pinfunction "1_1") (pintype "passive"))
    )
    (net (code "66") (name "Net-(R2-Pad1)") (class "Default")
      (node (ref "R2") (pin "1") (pinfunction "1_1") (pintype "passive"))
      (node (ref "RED_LED") (pin "2") (pinfunction "2_2") (pintype "passive"))
    )
    (net (code "67") (name "Net-(U$2A-CPH)") (class "Default")
      (node (ref "C13") (pin "1") (pinfunction "1_1") (pintype "passive"))
      (node (ref "U$2") (pin "1") (pinfunction "CPH_1") (pintype "passive"))
    )
    (net (code "68") (name "Net-(U$2A-CPL)") (class "Default")
      (node (ref "C13") (pin "2") (pinfunction "2_2") (pintype "passive"))
      (node (ref "U$2") (pin "32") (pinfunction "CPL_32") (pintype "passive"))
    )
    (net (code "69") (name "Net-(U$2A-IDRIVE)") (class "Default")
      (node (ref "R8") (pin "1") (pinfunction "1_1") (pintype "passive"))
      (node (ref "R9") (pin "2") (pinfunction "2_2") (pintype "passive"))
      (node (ref "U$2") (pin "19") (pinfunction "IDRIVE_19") (pintype "passive"))
    )
    (net (code "70") (name "Net-(U$2A-MODE)") (class "Default")
      (node (ref "R7") (pin "2") (pinfunction "2_2") (pintype "passive"))
      (node (ref "U$2") (pin "18") (pinfunction "MODE_18") (pintype "passive"))
    )
    (net (code "71") (name "Net-(U$2A-VDS)") (class "Default")
      (node (ref "R10") (pin "1") (pinfunction "1_1") (pintype "passive"))
      (node (ref "R11") (pin "2") (pinfunction "2_2") (pintype "passive"))
      (node (ref "U$2") (pin "20") (pinfunction "VDS_20") (pintype "passive"))
    )
    (net (code "72") (name "Net-(U$2B-VCP)") (class "Default")
      (node (ref "C17") (pin "1") (pinfunction "1_1") (pintype "passive"))
      (node (ref "U$2") (pin "2") (pinfunction "VCP_2") (pintype "passive"))
    )
    (net (code "73") (name "Net-(U$3A-CPH)") (class "Default")
      (node (ref "C19") (pin "1") (pinfunction "1_1") (pintype "passive"))
      (node (ref "U$3") (pin "1") (pinfunction "CPH_1") (pintype "passive"))
    )
    (net (code "74") (name "Net-(U$3A-CPL)") (class "Default")
      (node (ref "C19") (pin "2") (pinfunction "2_2") (pintype "passive"))
      (node (ref "U$3") (pin "32") (pinfunction "CPL_32") (pintype "passive"))
    )
    (net (code "75") (name "Net-(U$3A-IDRIVE)") (class "Default")
      (node (ref "R18") (pin "1") (pinfunction "1_1") (pintype "passive"))
      (node (ref "R19") (pin "2") (pinfunction "2_2") (pintype "passive"))
      (node (ref "U$3") (pin "19") (pinfunction "IDRIVE_19") (pintype "passive"))
    )
    (net (code "76") (name "Net-(U$3A-MODE)") (class "Default")
      (node (ref "R17") (pin "2") (pinfunction "2_2") (pintype "passive"))
      (node (ref "U$3") (pin "18") (pinfunction "MODE_18") (pintype "passive"))
    )
    (net (code "77") (name "Net-(U$3A-VDS)") (class "Default")
      (node (ref "R20") (pin "1") (pinfunction "1_1") (pintype "passive"))
      (node (ref "R21") (pin "2") (pinfunction "2_2") (pintype "passive"))
      (node (ref "U$3") (pin "20") (pinfunction "VDS_20") (pintype "passive"))
    )
    (net (code "78") (name "Net-(U$3B-VCP)") (class "Default")
      (node (ref "C22") (pin "1") (pinfunction "1_1") (pintype "passive"))
      (node (ref "U$3") (pin "2") (pinfunction "VCP_2") (pintype "passive"))
    )
    (net (code "79") (name "Net-(U$4A-CPH)") (class "Default")
      (node (ref "C23") (pin "1") (pinfunction "1_1") (pintype "passive"))
      (node (ref "U$4") (pin "1") (pinfunction "CPH_1") (pintype "passive"))
    )
    (net (code "80") (name "Net-(U$4A-CPL)") (class "Default")
      (node (ref "C23") (pin "2") (pinfunction "2_2") (pintype "passive"))
      (node (ref "U$4") (pin "32") (pinfunction "CPL_32") (pintype "passive"))
    )
    (net (code "81") (name "Net-(U$4A-IDRIVE)") (class "Default")
      (node (ref "R23") (pin "1") (pinfunction "1_1") (pintype "passive"))
      (node (ref "R24") (pin "2") (pinfunction "2_2") (pintype "passive"))
      (node (ref "U$4") (pin "19") (pinfunction "IDRIVE_19") (pintype "passive"))
    )
    (net (code "82") (name "Net-(U$4A-MODE)") (class "Default")
      (node (ref "R22") (pin "2") (pinfunction "2_2") (pintype "passive"))
      (node (ref "U$4") (pin "18") (pinfunction "MODE_18") (pintype "passive"))
    )
    (net (code "83") (name "Net-(U$4A-VDS)") (class "Default")
      (node (ref "R25") (pin "1") (pinfunction "1_1") (pintype "passive"))
      (node (ref "R26") (pin "2") (pinfunction "2_2") (pintype "passive"))
      (node (ref "U$4") (pin "20") (pinfunction "VDS_20") (pintype "passive"))
    )
    (net (code "84") (name "Net-(U$4B-VCP)") (class "Default")
      (node (ref "C26") (pin "1") (pinfunction "1_1") (pintype "passive"))
      (node (ref "U$4") (pin "2") (pinfunction "VCP_2") (pintype "passive"))
    )
    (net (code "85") (name "Net-(U$7A-CPH)") (class "Default")
      (node (ref "C27") (pin "1") (pinfunction "1_1") (pintype "passive"))
      (node (ref "U$7") (pin "1") (pinfunction "CPH_1") (pintype "passive"))
    )
    (net (code "86") (name "Net-(U$7A-CPL)") (class "Default")
      (node (ref "C27") (pin "2") (pinfunction "2_2") (pintype "passive"))
      (node (ref "U$7") (pin "32") (pinfunction "CPL_32") (pintype "passive"))
    )
    (net (code "87") (name "Net-(U$7A-IDRIVE)") (class "Default")
      (node (ref "R30") (pin "1") (pinfunction "1_1") (pintype "passive"))
      (node (ref "R31") (pin "2") (pinfunction "2_2") (pintype "passive"))
      (node (ref "U$7") (pin "19") (pinfunction "IDRIVE_19") (pintype "passive"))
    )
    (net (code "88") (name "Net-(U$7A-MODE)") (class "Default")
      (node (ref "R27") (pin "2") (pinfunction "2_2") (pintype "passive"))
      (node (ref "U$7") (pin "18") (pinfunction "MODE_18") (pintype "passive"))
    )
    (net (code "89") (name "Net-(U$7A-VDS)") (class "Default")
      (node (ref "R32") (pin "1") (pinfunction "1_1") (pintype "passive"))
      (node (ref "R33") (pin "2") (pinfunction "2_2") (pintype "passive"))
      (node (ref "U$7") (pin "20") (pinfunction "VDS_20") (pintype "passive"))
    )
    (net (code "90") (name "Net-(U$7B-VCP)") (class "Default")
      (node (ref "C36") (pin "1") (pinfunction "1_1") (pintype "passive"))
      (node (ref "U$7") (pin "2") (pinfunction "VCP_2") (pintype "passive"))
    )
    (net (code "91") (name "Net-(U1-PC4)") (class "Default")
      (node (ref "R1") (pin "2") (pinfunction "2_2") (pintype "passive"))
      (node (ref "U1") (pin "24") (pinfunction "PC4_24") (pintype "bidirectional"))
    )
    (net (code "92") (name "Net-(U1-PC5)") (class "Default")
      (node (ref "R2") (pin "2") (pinfunction "2_2") (pintype "passive"))
      (node (ref "U1") (pin "25") (pinfunction "PC5_25") (pintype "bidirectional"))
    )
    (net (code "93") (name "Net-(U1-VSS_1)") (class "Default")
      (node (ref "C3") (pin "1") (pinfunction "1_1") (pintype "passive"))
      (node (ref "U1") (pin "31") (pinfunction "VSS_1_31") (pintype "power_in"))
    )
    (net (code "94") (name "Net-(U1-VSS_2)") (class "Default")
      (node (ref "C1") (pin "1") (pinfunction "1_1") (pintype "passive"))
      (node (ref "U1") (pin "47") (pinfunction "VSS_2_47") (pintype "power_in"))
    )
    (net (code "95") (name "Net-(U14-OE)") (class "Default")
      (node (ref "R6") (pin "1") (pinfunction "1_1") (pintype "passive"))
      (node (ref "U14") (pin "P$15") (pinfunction "OE_P$15") (pintype "bidirectional"))
    )
    (net (code "96") (name "OSC_IN") (class "Default")
      (node (ref "R5") (pin "2") (pinfunction "2_2") (pintype "passive"))
      (node (ref "U1") (pin "5") (pinfunction "PD0_OSC_IN_5") (pintype "input"))
    )
    (net (code "97") (name "OSC_OUT") (class "Default")
      (node (ref "R3") (pin "2") (pinfunction "2_2") (pintype "passive"))
      (node (ref "U1") (pin "6") (pinfunction "PD1_OSC_OUT_6") (pintype "output"))
    )
    (net (code "98") (name "PHASE_A1") (class "Default")
      (node (ref "J2") (pin "1") (pinfunction "1_1") (pintype "passive"))
      (node (ref "U3") (pin "10") (pinfunction "VSW_9_10") (pintype "passive"))
      (node (ref "U3") (pin "11") (pinfunction "VSW_11") (pintype "passive"))
      (node (ref "U3") (pin "3") (pinfunction "VSW_2_3") (pintype "passive"))
      (node (ref "U3") (pin "4") (pinfunction "VSW_3_4") (pintype "passive"))
      (node (ref "U3") (pin "5") (pinfunction "VSW_4_5") (pintype "passive"))
      (node (ref "U3") (pin "6") (pinfunction "VSW_5_6") (pintype "passive"))
      (node (ref "U3") (pin "7") (pinfunction "VSW_6_7") (pintype "passive"))
      (node (ref "U3") (pin "8") (pinfunction "VSW_7_8") (pintype "passive"))
      (node (ref "U3") (pin "9") (pinfunction "VSW_8_9") (pintype "passive"))
    )
    (net (code "99") (name "PHASE_A2") (class "Default")
      (node (ref "J1") (pin "1") (pinfunction "1_1") (pintype "passive"))
      (node (ref "U9") (pin "10") (pinfunction "VSW_9_10") (pintype "passive"))
      (node (ref "U9") (pin "11") (pinfunction "VSW_11") (pintype "passive"))
      (node (ref "U9") (pin "3") (pinfunction "VSW_2_3") (pintype "passive"))
      (node (ref "U9") (pin "4") (pinfunction "VSW_3_4") (pintype "passive"))
      (node (ref "U9") (pin "5") (pinfunction "VSW_4_5") (pintype "passive"))
      (node (ref "U9") (pin "6") (pinfunction "VSW_5_6") (pintype "passive"))
      (node (ref "U9") (pin "7") (pinfunction "VSW_6_7") (pintype "passive"))
      (node (ref "U9") (pin "8") (pinfunction "VSW_7_8") (pintype "passive"))
      (node (ref "U9") (pin "9") (pinfunction "VSW_8_9") (pintype "passive"))
    )
    (net (code "100") (name "PHASE_A3") (class "Default")
      (node (ref "J3") (pin "1") (pinfunction "1_1") (pintype "passive"))
      (node (ref "U12") (pin "10") (pinfunction "VSW_9_10") (pintype "passive"))
      (node (ref "U12") (pin "11") (pinfunction "VSW_11") (pintype "passive"))
      (node (ref "U12") (pin "3") (pinfunction "VSW_2_3") (pintype "passive"))
      (node (ref "U12") (pin "4") (pinfunction "VSW_3_4") (pintype "passive"))
      (node (ref "U12") (pin "5") (pinfunction "VSW_4_5") (pintype "passive"))
      (node (ref "U12") (pin "6") (pinfunction "VSW_5_6") (pintype "passive"))
      (node (ref "U12") (pin "7") (pinfunction "VSW_6_7") (pintype "passive"))
      (node (ref "U12") (pin "8") (pinfunction "VSW_7_8") (pintype "passive"))
      (node (ref "U12") (pin "9") (pinfunction "VSW_8_9") (pintype "passive"))
    )
    (net (code "101") (name "PHASE_A4") (class "Default")
      (node (ref "J4") (pin "1") (pinfunction "1_1") (pintype "passive"))
      (node (ref "U16") (pin "10") (pinfunction "VSW_9_10") (pintype "passive"))
      (node (ref "U16") (pin "11") (pinfunction "VSW_11") (pintype "passive"))
      (node (ref "U16") (pin "3") (pinfunction "VSW_2_3") (pintype "passive"))
      (node (ref "U16") (pin "4") (pinfunction "VSW_3_4") (pintype "passive"))
      (node (ref "U16") (pin "5") (pinfunction "VSW_4_5") (pintype "passive"))
      (node (ref "U16") (pin "6") (pinfunction "VSW_5_6") (pintype "passive"))
      (node (ref "U16") (pin "7") (pinfunction "VSW_6_7") (pintype "passive"))
      (node (ref "U16") (pin "8") (pinfunction "VSW_7_8") (pintype "passive"))
      (node (ref "U16") (pin "9") (pinfunction "VSW_8_9") (pintype "passive"))
    )
    (net (code "102") (name "PHASE_B1") (class "Default")
      (node (ref "J2") (pin "2") (pinfunction "2_2") (pintype "passive"))
      (node (ref "U4") (pin "10") (pinfunction "VSW_9_10") (pintype "passive"))
      (node (ref "U4") (pin "11") (pinfunction "VSW_11") (pintype "passive"))
      (node (ref "U4") (pin "3") (pinfunction "VSW_2_3") (pintype "passive"))
      (node (ref "U4") (pin "4") (pinfunction "VSW_3_4") (pintype "passive"))
      (node (ref "U4") (pin "5") (pinfunction "VSW_4_5") (pintype "passive"))
      (node (ref "U4") (pin "6") (pinfunction "VSW_5_6") (pintype "passive"))
      (node (ref "U4") (pin "7") (pinfunction "VSW_6_7") (pintype "passive"))
      (node (ref "U4") (pin "8") (pinfunction "VSW_7_8") (pintype "passive"))
      (node (ref "U4") (pin "9") (pinfunction "VSW_8_9") (pintype "passive"))
    )
    (net (code "103") (name "PHASE_B2") (class "Default")
      (node (ref "J1") (pin "2") (pinfunction "2_2") (pintype "passive"))
      (node (ref "U10") (pin "10") (pinfunction "VSW_9_10") (pintype "passive"))
      (node (ref "U10") (pin "11") (pinfunction "VSW_11") (pintype "passive"))
      (node (ref "U10") (pin "3") (pinfunction "VSW_2_3") (pintype "passive"))
      (node (ref "U10") (pin "4") (pinfunction "VSW_3_4") (pintype "passive"))
      (node (ref "U10") (pin "5") (pinfunction "VSW_4_5") (pintype "passive"))
      (node (ref "U10") (pin "6") (pinfunction "VSW_5_6") (pintype "passive"))
      (node (ref "U10") (pin "7") (pinfunction "VSW_6_7") (pintype "passive"))
      (node (ref "U10") (pin "8") (pinfunction "VSW_7_8") (pintype "passive"))
      (node (ref "U10") (pin "9") (pinfunction "VSW_8_9") (pintype "passive"))
    )
    (net (code "104") (name "PHASE_B3") (class "Default")
      (node (ref "J3") (pin "2") (pinfunction "2_2") (pintype "passive"))
      (node (ref "U13") (pin "10") (pinfunction "VSW_9_10") (pintype "passive"))
      (node (ref "U13") (pin "11") (pinfunction "VSW_11") (pintype "passive"))
      (node (ref "U13") (pin "3") (pinfunction "VSW_2_3") (pintype "passive"))
      (node (ref "U13") (pin "4") (pinfunction "VSW_3_4") (pintype "passive"))
      (node (ref "U13") (pin "5") (pinfunction "VSW_4_5") (pintype "passive"))
      (node (ref "U13") (pin "6") (pinfunction "VSW_5_6") (pintype "passive"))
      (node (ref "U13") (pin "7") (pinfunction "VSW_6_7") (pintype "passive"))
      (node (ref "U13") (pin "8") (pinfunction "VSW_7_8") (pintype "passive"))
      (node (ref "U13") (pin "9") (pinfunction "VSW_8_9") (pintype "passive"))
    )
    (net (code "105") (name "PHASE_B4") (class "Default")
      (node (ref "J4") (pin "2") (pinfunction "2_2") (pintype "passive"))
      (node (ref "U17") (pin "10") (pinfunction "VSW_9_10") (pintype "passive"))
      (node (ref "U17") (pin "11") (pinfunction "VSW_11") (pintype "passive"))
      (node (ref "U17") (pin "3") (pinfunction "VSW_2_3") (pintype "passive"))
      (node (ref "U17") (pin "4") (pinfunction "VSW_3_4") (pintype "passive"))
      (node (ref "U17") (pin "5") (pinfunction "VSW_4_5") (pintype "passive"))
      (node (ref "U17") (pin "6") (pinfunction "VSW_5_6") (pintype "passive"))
      (node (ref "U17") (pin "7") (pinfunction "VSW_6_7") (pintype "passive"))
      (node (ref "U17") (pin "8") (pinfunction "VSW_7_8") (pintype "passive"))
      (node (ref "U17") (pin "9") (pinfunction "VSW_8_9") (pintype "passive"))
    )
    (net (code "106") (name "PHASE_C1") (class "Default")
      (node (ref "J2") (pin "3") (pinfunction "3_3") (pintype "passive"))
      (node (ref "U2") (pin "10") (pinfunction "VSW_9_10") (pintype "passive"))
      (node (ref "U2") (pin "11") (pinfunction "VSW_11") (pintype "passive"))
      (node (ref "U2") (pin "3") (pinfunction "VSW_2_3") (pintype "passive"))
      (node (ref "U2") (pin "4") (pinfunction "VSW_3_4") (pintype "passive"))
      (node (ref "U2") (pin "5") (pinfunction "VSW_4_5") (pintype "passive"))
      (node (ref "U2") (pin "6") (pinfunction "VSW_5_6") (pintype "passive"))
      (node (ref "U2") (pin "7") (pinfunction "VSW_6_7") (pintype "passive"))
      (node (ref "U2") (pin "8") (pinfunction "VSW_7_8") (pintype "passive"))
      (node (ref "U2") (pin "9") (pinfunction "VSW_8_9") (pintype "passive"))
    )
    (net (code "107") (name "PHASE_C2") (class "Default")
      (node (ref "J1") (pin "3") (pinfunction "3_3") (pintype "passive"))
      (node (ref "U8") (pin "10") (pinfunction "VSW_9_10") (pintype "passive"))
      (node (ref "U8") (pin "11") (pinfunction "VSW_11") (pintype "passive"))
      (node (ref "U8") (pin "3") (pinfunction "VSW_2_3") (pintype "passive"))
      (node (ref "U8") (pin "4") (pinfunction "VSW_3_4") (pintype "passive"))
      (node (ref "U8") (pin "5") (pinfunction "VSW_4_5") (pintype "passive"))
      (node (ref "U8") (pin "6") (pinfunction "VSW_5_6") (pintype "passive"))
      (node (ref "U8") (pin "7") (pinfunction "VSW_6_7") (pintype "passive"))
      (node (ref "U8") (pin "8") (pinfunction "VSW_7_8") (pintype "passive"))
      (node (ref "U8") (pin "9") (pinfunction "VSW_8_9") (pintype "passive"))
    )
    (net (code "108") (name "PHASE_C3") (class "Default")
      (node (ref "J3") (pin "3") (pinfunction "3_3") (pintype "passive"))
      (node (ref "U11") (pin "10") (pinfunction "VSW_9_10") (pintype "passive"))
      (node (ref "U11") (pin "11") (pinfunction "VSW_11") (pintype "passive"))
      (node (ref "U11") (pin "3") (pinfunction "VSW_2_3") (pintype "passive"))
      (node (ref "U11") (pin "4") (pinfunction "VSW_3_4") (pintype "passive"))
      (node (ref "U11") (pin "5") (pinfunction "VSW_4_5") (pintype "passive"))
      (node (ref "U11") (pin "6") (pinfunction "VSW_5_6") (pintype "passive"))
      (node (ref "U11") (pin "7") (pinfunction "VSW_6_7") (pintype "passive"))
      (node (ref "U11") (pin "8") (pinfunction "VSW_7_8") (pintype "passive"))
      (node (ref "U11") (pin "9") (pinfunction "VSW_8_9") (pintype "passive"))
    )
    (net (code "109") (name "PHASE_C4") (class "Default")
      (node (ref "J4") (pin "3") (pinfunction "3_3") (pintype "passive"))
      (node (ref "U15") (pin "10") (pinfunction "VSW_9_10") (pintype "passive"))
      (node (ref "U15") (pin "11") (pinfunction "VSW_11") (pintype "passive"))
      (node (ref "U15") (pin "3") (pinfunction "VSW_2_3") (pintype "passive"))
      (node (ref "U15") (pin "4") (pinfunction "VSW_3_4") (pintype "passive"))
      (node (ref "U15") (pin "5") (pinfunction "VSW_4_5") (pintype "passive"))
      (node (ref "U15") (pin "6") (pinfunction "VSW_5_6") (pintype "passive"))
      (node (ref "U15") (pin "7") (pinfunction "VSW_6_7") (pintype "passive"))
      (node (ref "U15") (pin "8") (pinfunction "VSW_7_8") (pintype "passive"))
      (node (ref "U15") (pin "9") (pinfunction "VSW_8_9") (pintype "passive"))
    )
    (net (code "110") (name "PROG_SEL") (class "Default")
      (node (ref "U$5") (pin "P$5") (pinfunction "P$5_P$5") (pintype "bidirectional"))
    )
    (net (code "111") (name "S") (class "Default")
      (node (ref "U$6") (pin "S") (pinfunction "S_S") (pintype "bidirectional"))
      (node (ref "U14") (pin "P$1") (pinfunction "S_P$1") (pintype "bidirectional"))
    )
    (net (code "112") (name "SHA_1") (class "Default")
      (node (ref "U$2") (pin "6") (pinfunction "SHA_6") (pintype "passive"))
      (node (ref "U3") (pin "2") (pinfunction "SH_2") (pintype "passive"))
    )
    (net (code "113") (name "SHA_2") (class "Default")
      (node (ref "U$3") (pin "6") (pinfunction "SHA_6") (pintype "passive"))
      (node (ref "U9") (pin "2") (pinfunction "SH_2") (pintype "passive"))
    )
    (net (code "114") (name "SHA_3") (class "Default")
      (node (ref "U$4") (pin "6") (pinfunction "SHA_6") (pintype "passive"))
      (node (ref "U12") (pin "2") (pinfunction "SH_2") (pintype "passive"))
    )
    (net (code "115") (name "SHA_4") (class "Default")
      (node (ref "U$7") (pin "6") (pinfunction "SHA_6") (pintype "passive"))
      (node (ref "U16") (pin "2") (pinfunction "SH_2") (pintype "passive"))
    )
    (net (code "116") (name "SHB_1") (class "Default")
      (node (ref "U$2") (pin "11") (pinfunction "SHB_11") (pintype "passive"))
      (node (ref "U4") (pin "2") (pinfunction "SH_2") (pintype "passive"))
    )
    (net (code "117") (name "SHB_2") (class "Default")
      (node (ref "U$3") (pin "11") (pinfunction "SHB_11") (pintype "passive"))
      (node (ref "U10") (pin "2") (pinfunction "SH_2") (pintype "passive"))
    )
    (net (code "118") (name "SHB_3") (class "Default")
      (node (ref "U$4") (pin "11") (pinfunction "SHB_11") (pintype "passive"))
      (node (ref "U13") (pin "2") (pinfunction "SH_2") (pintype "passive"))
    )
    (net (code "119") (name "SHB_4") (class "Default")
      (node (ref "U$7") (pin "11") (pinfunction "SHB_11") (pintype "passive"))
      (node (ref "U17") (pin "2") (pinfunction "SH_2") (pintype "passive"))
    )
    (net (code "120") (name "SHC_1") (class "Default")
      (node (ref "U$2") (pin "14") (pinfunction "SHC_14") (pintype "passive"))
      (node (ref "U2") (pin "2") (pinfunction "SH_2") (pintype "passive"))
    )
    (net (code "121") (name "SHC_2") (class "Default")
      (node (ref "U$3") (pin "14") (pinfunction "SHC_14") (pintype "passive"))
      (node (ref "U8") (pin "2") (pinfunction "SH_2") (pintype "passive"))
    )
    (net (code "122") (name "SHC_3") (class "Default")
      (node (ref "U$4") (pin "14") (pinfunction "SHC_14") (pintype "passive"))
      (node (ref "U11") (pin "2") (pinfunction "SH_2") (pintype "passive"))
    )
    (net (code "123") (name "SHC_4") (class "Default")
      (node (ref "U$7") (pin "14") (pinfunction "SHC_14") (pintype "passive"))
      (node (ref "U15") (pin "2") (pinfunction "SH_2") (pintype "passive"))
    )
    (net (code "124") (name "SLA_1") (class "Default")
      (node (ref "U$2") (pin "8") (pinfunction "SLA_8") (pintype "passive"))
      (node (ref "U3") (pin "12") (pinfunction "PGND_2_12") (pintype "power_in"))
      (node (ref "U3") (pin "13") (pinfunction "PGND_3_13") (pintype "power_in"))
      (node (ref "U3") (pin "14") (pinfunction "PGND_4_14") (pintype "power_in"))
      (node (ref "U3") (pin "15") (pinfunction "PGND_5_15") (pintype "power_in"))
      (node (ref "U3") (pin "16") (pinfunction "PGND_6_16") (pintype "power_in"))
      (node (ref "U3") (pin "17") (pinfunction "PGND_7_17") (pintype "power_in"))
      (node (ref "U3") (pin "18") (pinfunction "PGND_8_18") (pintype "power_in"))
      (node (ref "U3") (pin "19") (pinfunction "PGND_9_19") (pintype "power_in"))
      (node (ref "U3") (pin "20") (pinfunction "PGND_20") (pintype "power_in"))
    )
    (net (code "125") (name "SLA_2") (class "Default")
      (node (ref "U$3") (pin "8") (pinfunction "SLA_8") (pintype "passive"))
      (node (ref "U9") (pin "12") (pinfunction "PGND_2_12") (pintype "power_in"))
      (node (ref "U9") (pin "13") (pinfunction "PGND_3_13") (pintype "power_in"))
      (node (ref "U9") (pin "14") (pinfunction "PGND_4_14") (pintype "power_in"))
      (node (ref "U9") (pin "15") (pinfunction "PGND_5_15") (pintype "power_in"))
      (node (ref "U9") (pin "16") (pinfunction "PGND_6_16") (pintype "power_in"))
      (node (ref "U9") (pin "17") (pinfunction "PGND_7_17") (pintype "power_in"))
      (node (ref "U9") (pin "18") (pinfunction "PGND_8_18") (pintype "power_in"))
      (node (ref "U9") (pin "19") (pinfunction "PGND_9_19") (pintype "power_in"))
      (node (ref "U9") (pin "20") (pinfunction "PGND_20") (pintype "power_in"))
    )
    (net (code "126") (name "SLA_3") (class "Default")
      (node (ref "U$4") (pin "8") (pinfunction "SLA_8") (pintype "passive"))
      (node (ref "U12") (pin "12") (pinfunction "PGND_2_12") (pintype "power_in"))
      (node (ref "U12") (pin "13") (pinfunction "PGND_3_13") (pintype "power_in"))
      (node (ref "U12") (pin "14") (pinfunction "PGND_4_14") (pintype "power_in"))
      (node (ref "U12") (pin "15") (pinfunction "PGND_5_15") (pintype "power_in"))
      (node (ref "U12") (pin "16") (pinfunction "PGND_6_16") (pintype "power_in"))
      (node (ref "U12") (pin "17") (pinfunction "PGND_7_17") (pintype "power_in"))
      (node (ref "U12") (pin "18") (pinfunction "PGND_8_18") (pintype "power_in"))
      (node (ref "U12") (pin "19") (pinfunction "PGND_9_19") (pintype "power_in"))
      (node (ref "U12") (pin "20") (pinfunction "PGND_20") (pintype "power_in"))
    )
    (net (code "127") (name "SLA_4") (class "Default")
      (node (ref "U$7") (pin "8") (pinfunction "SLA_8") (pintype "passive"))
      (node (ref "U16") (pin "12") (pinfunction "PGND_2_12") (pintype "power_in"))
      (node (ref "U16") (pin "13") (pinfunction "PGND_3_13") (pintype "power_in"))
      (node (ref "U16") (pin "14") (pinfunction "PGND_4_14") (pintype "power_in"))
      (node (ref "U16") (pin "15") (pinfunction "PGND_5_15") (pintype "power_in"))
      (node (ref "U16") (pin "16") (pinfunction "PGND_6_16") (pintype "power_in"))
      (node (ref "U16") (pin "17") (pinfunction "PGND_7_17") (pintype "power_in"))
      (node (ref "U16") (pin "18") (pinfunction "PGND_8_18") (pintype "power_in"))
      (node (ref "U16") (pin "19") (pinfunction "PGND_9_19") (pintype "power_in"))
      (node (ref "U16") (pin "20") (pinfunction "PGND_20") (pintype "power_in"))
    )
    (net (code "128") (name "SLB_1") (class "Default")
      (node (ref "U$2") (pin "9") (pinfunction "SLB_9") (pintype "passive"))
      (node (ref "U4") (pin "12") (pinfunction "PGND_2_12") (pintype "power_in"))
      (node (ref "U4") (pin "13") (pinfunction "PGND_3_13") (pintype "power_in"))
      (node (ref "U4") (pin "14") (pinfunction "PGND_4_14") (pintype "power_in"))
      (node (ref "U4") (pin "15") (pinfunction "PGND_5_15") (pintype "power_in"))
      (node (ref "U4") (pin "16") (pinfunction "PGND_6_16") (pintype "power_in"))
      (node (ref "U4") (pin "17") (pinfunction "PGND_7_17") (pintype "power_in"))
      (node (ref "U4") (pin "18") (pinfunction "PGND_8_18") (pintype "power_in"))
      (node (ref "U4") (pin "19") (pinfunction "PGND_9_19") (pintype "power_in"))
      (node (ref "U4") (pin "20") (pinfunction "PGND_20") (pintype "power_in"))
    )
    (net (code "129") (name "SLB_2") (class "Default")
      (node (ref "U$3") (pin "9") (pinfunction "SLB_9") (pintype "passive"))
      (node (ref "U10") (pin "12") (pinfunction "PGND_2_12") (pintype "power_in"))
      (node (ref "U10") (pin "13") (pinfunction "PGND_3_13") (pintype "power_in"))
      (node (ref "U10") (pin "14") (pinfunction "PGND_4_14") (pintype "power_in"))
      (node (ref "U10") (pin "15") (pinfunction "PGND_5_15") (pintype "power_in"))
      (node (ref "U10") (pin "16") (pinfunction "PGND_6_16") (pintype "power_in"))
      (node (ref "U10") (pin "17") (pinfunction "PGND_7_17") (pintype "power_in"))
      (node (ref "U10") (pin "18") (pinfunction "PGND_8_18") (pintype "power_in"))
      (node (ref "U10") (pin "19") (pinfunction "PGND_9_19") (pintype "power_in"))
      (node (ref "U10") (pin "20") (pinfunction "PGND_20") (pintype "power_in"))
    )
    (net (code "130") (name "SLB_3") (class "Default")
      (node (ref "U$4") (pin "9") (pinfunction "SLB_9") (pintype "passive"))
      (node (ref "U13") (pin "12") (pinfunction "PGND_2_12") (pintype "power_in"))
      (node (ref "U13") (pin "13") (pinfunction "PGND_3_13") (pintype "power_in"))
      (node (ref "U13") (pin "14") (pinfunction "PGND_4_14") (pintype "power_in"))
      (node (ref "U13") (pin "15") (pinfunction "PGND_5_15") (pintype "power_in"))
      (node (ref "U13") (pin "16") (pinfunction "PGND_6_16") (pintype "power_in"))
      (node (ref "U13") (pin "17") (pinfunction "PGND_7_17") (pintype "power_in"))
      (node (ref "U13") (pin "18") (pinfunction "PGND_8_18") (pintype "power_in"))
      (node (ref "U13") (pin "19") (pinfunction "PGND_9_19") (pintype "power_in"))
      (node (ref "U13") (pin "20") (pinfunction "PGND_20") (pintype "power_in"))
    )
    (net (code "131") (name "SLB_4") (class "Default")
      (node (ref "U$7") (pin "9") (pinfunction "SLB_9") (pintype "passive"))
      (node (ref "U17") (pin "12") (pinfunction "PGND_2_12") (pintype "power_in"))
      (node (ref "U17") (pin "13") (pinfunction "PGND_3_13") (pintype "power_in"))
      (node (ref "U17") (pin "14") (pinfunction "PGND_4_14") (pintype "power_in"))
      (node (ref "U17") (pin "15") (pinfunction "PGND_5_15") (pintype "power_in"))
      (node (ref "U17") (pin "16") (pinfunction "PGND_6_16") (pintype "power_in"))
      (node (ref "U17") (pin "17") (pinfunction "PGND_7_17") (pintype "power_in"))
      (node (ref "U17") (pin "18") (pinfunction "PGND_8_18") (pintype "power_in"))
      (node (ref "U17") (pin "19") (pinfunction "PGND_9_19") (pintype "power_in"))
      (node (ref "U17") (pin "20") (pinfunction "PGND_20") (pintype "power_in"))
    )
    (net (code "132") (name "SLC_1") (class "Default")
      (node (ref "U$2") (pin "16") (pinfunction "SLC_16") (pintype "passive"))
      (node (ref "U2") (pin "12") (pinfunction "PGND_2_12") (pintype "power_in"))
      (node (ref "U2") (pin "13") (pinfunction "PGND_3_13") (pintype "power_in"))
      (node (ref "U2") (pin "14") (pinfunction "PGND_4_14") (pintype "power_in"))
      (node (ref "U2") (pin "15") (pinfunction "PGND_5_15") (pintype "power_in"))
      (node (ref "U2") (pin "16") (pinfunction "PGND_6_16") (pintype "power_in"))
      (node (ref "U2") (pin "17") (pinfunction "PGND_7_17") (pintype "power_in"))
      (node (ref "U2") (pin "18") (pinfunction "PGND_8_18") (pintype "power_in"))
      (node (ref "U2") (pin "19") (pinfunction "PGND_9_19") (pintype "power_in"))
      (node (ref "U2") (pin "20") (pinfunction "PGND_20") (pintype "power_in"))
    )
    (net (code "133") (name "SLC_2") (class "Default")
      (node (ref "U$3") (pin "16") (pinfunction "SLC_16") (pintype "passive"))
      (node (ref "U8") (pin "12") (pinfunction "PGND_2_12") (pintype "power_in"))
      (node (ref "U8") (pin "13") (pinfunction "PGND_3_13") (pintype "power_in"))
      (node (ref "U8") (pin "14") (pinfunction "PGND_4_14") (pintype "power_in"))
      (node (ref "U8") (pin "15") (pinfunction "PGND_5_15") (pintype "power_in"))
      (node (ref "U8") (pin "16") (pinfunction "PGND_6_16") (pintype "power_in"))
      (node (ref "U8") (pin "17") (pinfunction "PGND_7_17") (pintype "power_in"))
      (node (ref "U8") (pin "18") (pinfunction "PGND_8_18") (pintype "power_in"))
      (node (ref "U8") (pin "19") (pinfunction "PGND_9_19") (pintype "power_in"))
      (node (ref "U8") (pin "20") (pinfunction "PGND_20") (pintype "power_in"))
    )
    (net (code "134") (name "SLC_3") (class "Default")
      (node (ref "U$4") (pin "16") (pinfunction "SLC_16") (pintype "passive"))
      (node (ref "U11") (pin "12") (pinfunction "PGND_2_12") (pintype "power_in"))
      (node (ref "U11") (pin "13") (pinfunction "PGND_3_13") (pintype "power_in"))
      (node (ref "U11") (pin "14") (pinfunction "PGND_4_14") (pintype "power_in"))
      (node (ref "U11") (pin "15") (pinfunction "PGND_5_15") (pintype "power_in"))
      (node (ref "U11") (pin "16") (pinfunction "PGND_6_16") (pintype "power_in"))
      (node (ref "U11") (pin "17") (pinfunction "PGND_7_17") (pintype "power_in"))
      (node (ref "U11") (pin "18") (pinfunction "PGND_8_18") (pintype "power_in"))
      (node (ref "U11") (pin "19") (pinfunction "PGND_9_19") (pintype "power_in"))
      (node (ref "U11") (pin "20") (pinfunction "PGND_20") (pintype "power_in"))
    )
    (net (code "135") (name "SLC_4") (class "Default")
      (node (ref "U$7") (pin "16") (pinfunction "SLC_16") (pintype "passive"))
      (node (ref "U15") (pin "12") (pinfunction "PGND_2_12") (pintype "power_in"))
      (node (ref "U15") (pin "13") (pinfunction "PGND_3_13") (pintype "power_in"))
      (node (ref "U15") (pin "14") (pinfunction "PGND_4_14") (pintype "power_in"))
      (node (ref "U15") (pin "15") (pinfunction "PGND_5_15") (pintype "power_in"))
      (node (ref "U15") (pin "16") (pinfunction "PGND_6_16") (pintype "power_in"))
      (node (ref "U15") (pin "17") (pinfunction "PGND_7_17") (pintype "power_in"))
      (node (ref "U15") (pin "18") (pinfunction "PGND_8_18") (pintype "power_in"))
      (node (ref "U15") (pin "19") (pinfunction "PGND_9_19") (pintype "power_in"))
      (node (ref "U15") (pin "20") (pinfunction "PGND_20") (pintype "power_in"))
    )
    (net (code "136") (name "SWCLK") (class "Default")
      (node (ref "SV2") (pin "4") (pinfunction "4_4") (pintype "passive"))
      (node (ref "U1") (pin "49") (pinfunction "PA14_49") (pintype "bidirectional"))
      (node (ref "U14") (pin "P$2") (pinfunction "1B1_P$2") (pintype "bidirectional"))
    )
    (net (code "137") (name "SWCLK_IN") (class "Default")
      (node (ref "U14") (pin "P$4") (pinfunction "1A_P$4") (pintype "bidirectional"))
    )
    (net (code "138") (name "SWDIO") (class "Default")
      (node (ref "SV2") (pin "2") (pinfunction "2_2") (pintype "passive"))
      (node (ref "U1") (pin "46") (pinfunction "PA13_46") (pintype "bidirectional"))
      (node (ref "U14") (pin "P$5") (pinfunction "2B1_P$5") (pintype "bidirectional"))
    )
    (net (code "139") (name "SWDIO_IN") (class "Default")
      (node (ref "U14") (pin "P$7") (pinfunction "2A_P$7") (pintype "bidirectional"))
    )
    (net (code "140") (name "VM_1") (class "Default")
      (node (ref "C15") (pin "1") (pinfunction "1_1") (pintype "passive"))
      (node (ref "C17") (pin "2") (pinfunction "2_2") (pintype "passive"))
      (node (ref "U$2") (pin "3") (pinfunction "VM_3") (pintype "passive"))
      (node (ref "U$2") (pin "4") (pinfunction "VDRAIN_4") (pintype "passive"))
      (node (ref "U2") (pin "27") (pinfunction "VIN_27") (pintype "power_in"))
      (node (ref "U3") (pin "27") (pinfunction "VIN_27") (pintype "power_in"))
      (node (ref "U4") (pin "27") (pinfunction "VIN_27") (pintype "power_in"))
    )
    (net (code "141") (name "VM_2") (class "Default")
      (node (ref "C21") (pin "1") (pinfunction "1_1") (pintype "passive"))
      (node (ref "C22") (pin "2") (pinfunction "2_2") (pintype "passive"))
      (node (ref "U$3") (pin "3") (pinfunction "VM_3") (pintype "passive"))
      (node (ref "U$3") (pin "4") (pinfunction "VDRAIN_4") (pintype "passive"))
      (node (ref "U10") (pin "27") (pinfunction "VIN_27") (pintype "power_in"))
      (node (ref "U8") (pin "27") (pinfunction "VIN_27") (pintype "power_in"))
      (node (ref "U9") (pin "27") (pinfunction "VIN_27") (pintype "power_in"))
    )
    (net (code "142") (name "VM_3") (class "Default")
      (node (ref "C25") (pin "1") (pinfunction "1_1") (pintype "passive"))
      (node (ref "C26") (pin "2") (pinfunction "2_2") (pintype "passive"))
      (node (ref "U$4") (pin "3") (pinfunction "VM_3") (pintype "passive"))
      (node (ref "U$4") (pin "4") (pinfunction "VDRAIN_4") (pintype "passive"))
      (node (ref "U11") (pin "27") (pinfunction "VIN_27") (pintype "power_in"))
      (node (ref "U12") (pin "27") (pinfunction "VIN_27") (pintype "power_in"))
      (node (ref "U13") (pin "27") (pinfunction "VIN_27") (pintype "power_in"))
    )
    (net (code "143") (name "VM_4") (class "Default")
      (node (ref "C29") (pin "1") (pinfunction "1_1") (pintype "passive"))
      (node (ref "C36") (pin "2") (pinfunction "2_2") (pintype "passive"))
      (node (ref "U$7") (pin "3") (pinfunction "VM_3") (pintype "passive"))
      (node (ref "U$7") (pin "4") (pinfunction "VDRAIN_4") (pintype "passive"))
      (node (ref "U15") (pin "27") (pinfunction "VIN_27") (pintype "power_in"))
      (node (ref "U16") (pin "27") (pinfunction "VIN_27") (pintype "power_in"))
      (node (ref "U17") (pin "27") (pinfunction "VIN_27") (pintype "power_in"))
    )
    (net (code "144") (name "unconnected-(U$2B-NC-Pad21)") (class "Default")
      (node (ref "U$2") (pin "21") (pinfunction "NC_21") (pintype "passive"))
    )
    (net (code "145") (name "unconnected-(U$3B-NC-Pad21)") (class "Default")
      (node (ref "U$3") (pin "21") (pinfunction "NC_21") (pintype "passive"))
    )
    (net (code "146") (name "unconnected-(U$4B-NC-Pad21)") (class "Default")
      (node (ref "U$4") (pin "21") (pinfunction "NC_21") (pintype "passive"))
    )
    (net (code "147") (name "unconnected-(U$5-PadP$8)") (class "Default")
      (node (ref "U$5") (pin "P$8") (pinfunction "P$8_P$8") (pintype "bidirectional"))
    )
    (net (code "148") (name "unconnected-(U$5-PadP$19)") (class "Default")
      (node (ref "U$5") (pin "P$19") (pinfunction "P$19_P$19") (pintype "bidirectional"))
    )
    (net (code "149") (name "unconnected-(U$5-PadP$20)") (class "Default")
      (node (ref "U$5") (pin "P$20") (pinfunction "P$20_P$20") (pintype "bidirectional"))
    )
    (net (code "150") (name "unconnected-(U$5-PadP$21)") (class "Default")
      (node (ref "U$5") (pin "P$21") (pinfunction "P$21_P$21") (pintype "bidirectional"))
    )
    (net (code "151") (name "unconnected-(U$5-PadP$22)") (class "Default")
      (node (ref "U$5") (pin "P$22") (pinfunction "P$22_P$22") (pintype "bidirectional"))
    )
    (net (code "152") (name "unconnected-(U$5-PadP$F)") (class "Default")
      (node (ref "U$5") (pin "P$F") (pinfunction "P$F_P$F") (pintype "bidirectional"))
    )
    (net (code "153") (name "unconnected-(U$5-PadP$I)") (class "Default")
      (node (ref "U$5") (pin "P$I") (pinfunction "P$I_P$I") (pintype "bidirectional"))
    )
    (net (code "154") (name "unconnected-(U$5-PadP$T)") (class "Default")
      (node (ref "U$5") (pin "P$T") (pinfunction "P$T_P$T") (pintype "bidirectional"))
    )
    (net (code "155") (name "unconnected-(U$5-PadP$W)") (class "Default")
      (node (ref "U$5") (pin "P$W") (pinfunction "P$W_P$W") (pintype "bidirectional"))
    )
    (net (code "156") (name "unconnected-(U$6-PadFAULT)") (class "Default")
      (node (ref "U$6") (pin "FAULT") (pinfunction "FAULT_FAULT") (pintype "bidirectional"))
    )
    (net (code "157") (name "unconnected-(U$7B-NC-Pad21)") (class "Default")
      (node (ref "U$7") (pin "21") (pinfunction "NC_21") (pintype "passive"))
    )
    (net (code "158") (name "unconnected-(U1-PA0-WKUP-Pad14)") (class "Default")
      (node (ref "U1") (pin "14") (pinfunction "PA0-WKUP_14") (pintype "bidirectional"))
    )
    (net (code "159") (name "unconnected-(U1-PA1-Pad15)") (class "Default")
      (node (ref "U1") (pin "15") (pinfunction "PA1_15") (pintype "bidirectional"))
    )
    (net (code "160") (name "unconnected-(U1-PA2-Pad16)") (class "Default")
      (node (ref "U1") (pin "16") (pinfunction "PA2_16") (pintype "bidirectional"))
    )
    (net (code "161") (name "unconnected-(U1-PA3-Pad17)") (class "Default")
      (node (ref "U1") (pin "17") (pinfunction "PA3_17") (pintype "bidirectional"))
    )
    (net (code "162") (name "unconnected-(U1-PA4-Pad20)") (class "Default")
      (node (ref "U1") (pin "20") (pinfunction "PA4_20") (pintype "bidirectional"))
    )
    (net (code "163") (name "unconnected-(U1-PA5-Pad21)") (class "Default")
      (node (ref "U1") (pin "21") (pinfunction "PA5_21") (pintype "bidirectional"))
    )
    (net (code "164") (name "unconnected-(U1-PA6-Pad22)") (class "Default")
      (node (ref "U1") (pin "22") (pinfunction "PA6_22") (pintype "bidirectional"))
    )
    (net (code "165") (name "unconnected-(U1-PA7-Pad23)") (class "Default")
      (node (ref "U1") (pin "23") (pinfunction "PA7_23") (pintype "bidirectional"))
    )
    (net (code "166") (name "unconnected-(U1-PA12-Pad45)") (class "Default")
      (node (ref "U1") (pin "45") (pinfunction "PA12_45") (pintype "bidirectional"))
    )
    (net (code "167") (name "unconnected-(U1-PB0-Pad26)") (class "Default")
      (node (ref "U1") (pin "26") (pinfunction "PB0_26") (pintype "bidirectional"))
    )
    (net (code "168") (name "unconnected-(U1-PB10-Pad29)") (class "Default")
      (node (ref "U1") (pin "29") (pinfunction "PB10_29") (pintype "bidirectional"))
    )
    (net (code "169") (name "unconnected-(U1-PB11-Pad30)") (class "Default")
      (node (ref "U1") (pin "30") (pinfunction "PB11_30") (pintype "bidirectional"))
    )
    (net (code "170") (name "unconnected-(U1-PC0-Pad8)") (class "Default")
      (node (ref "U1") (pin "8") (pinfunction "PC0_8") (pintype "bidirectional"))
    )
    (net (code "171") (name "unconnected-(U1-PC1-Pad9)") (class "Default")
      (node (ref "U1") (pin "9") (pinfunction "PC1_9") (pintype "bidirectional"))
    )
    (net (code "172") (name "unconnected-(U1-PC2-Pad10)") (class "Default")
      (node (ref "U1") (pin "10") (pinfunction "PC2_10") (pintype "bidirectional"))
    )
    (net (code "173") (name "unconnected-(U1-PC3-Pad11)") (class "Default")
      (node (ref "U1") (pin "11") (pinfunction "PC3_11") (pintype "bidirectional"))
    )
    (net (code "174") (name "unconnected-(U1-PC13-TAMPER-RTC-Pad2)") (class "Default")
      (node (ref "U1") (pin "2") (pinfunction "PC13-TAMPER-RTC_2") (pintype "bidirectional"))
    )
    (net (code "175") (name "unconnected-(U1-PC14-OSC32_IN-Pad3)") (class "Default")
      (node (ref "U1") (pin "3") (pinfunction "PC14-OSC32_IN_3") (pintype "bidirectional"))
    )
    (net (code "176") (name "unconnected-(U1-PC15-OSC32_OUT-Pad4)") (class "Default")
      (node (ref "U1") (pin "4") (pinfunction "PC15-OSC32_OUT_4") (pintype "bidirectional"))
    )
    (net (code "177") (name "unconnected-(U2-NC-Pad26)") (class "Default")
      (node (ref "U2") (pin "26") (pinfunction "NC_26") (pintype "passive"))
    )
    (net (code "178") (name "unconnected-(U2-NC_2-Pad21)") (class "Default")
      (node (ref "U2") (pin "21") (pinfunction "NC_2_21") (pintype "passive"))
    )
    (net (code "179") (name "unconnected-(U2-NC_3-Pad23)") (class "Default")
      (node (ref "U2") (pin "23") (pinfunction "NC_3_23") (pintype "passive"))
    )
    (net (code "180") (name "unconnected-(U2-NC_4-Pad24)") (class "Default")
      (node (ref "U2") (pin "24") (pinfunction "NC_4_24") (pintype "passive"))
    )
    (net (code "181") (name "unconnected-(U2-NC_5-Pad25)") (class "Default")
      (node (ref "U2") (pin "25") (pinfunction "NC_5_25") (pintype "passive"))
    )
    (net (code "182") (name "unconnected-(U3-NC-Pad26)") (class "Default")
      (node (ref "U3") (pin "26") (pinfunction "NC_26") (pintype "passive"))
    )
    (net (code "183") (name "unconnected-(U3-NC_2-Pad21)") (class "Default")
      (node (ref "U3") (pin "21") (pinfunction "NC_2_21") (pintype "passive"))
    )
    (net (code "184") (name "unconnected-(U3-NC_3-Pad23)") (class "Default")
      (node (ref "U3") (pin "23") (pinfunction "NC_3_23") (pintype "passive"))
    )
    (net (code "185") (name "unconnected-(U3-NC_4-Pad24)") (class "Default")
      (node (ref "U3") (pin "24") (pinfunction "NC_4_24") (pintype "passive"))
    )
    (net (code "186") (name "unconnected-(U3-NC_5-Pad25)") (class "Default")
      (node (ref "U3") (pin "25") (pinfunction "NC_5_25") (pintype "passive"))
    )
    (net (code "187") (name "unconnected-(U4-NC-Pad26)") (class "Default")
      (node (ref "U4") (pin "26") (pinfunction "NC_26") (pintype "passive"))
    )
    (net (code "188") (name "unconnected-(U4-NC_2-Pad21)") (class "Default")
      (node (ref "U4") (pin "21") (pinfunction "NC_2_21") (pintype "passive"))
    )
    (net (code "189") (name "unconnected-(U4-NC_3-Pad23)") (class "Default")
      (node (ref "U4") (pin "23") (pinfunction "NC_3_23") (pintype "passive"))
    )
    (net (code "190") (name "unconnected-(U4-NC_4-Pad24)") (class "Default")
      (node (ref "U4") (pin "24") (pinfunction "NC_4_24") (pintype "passive"))
    )
    (net (code "191") (name "unconnected-(U4-NC_5-Pad25)") (class "Default")
      (node (ref "U4") (pin "25") (pinfunction "NC_5_25") (pintype "passive"))
    )
    (net (code "192") (name "unconnected-(U8-NC-Pad26)") (class "Default")
      (node (ref "U8") (pin "26") (pinfunction "NC_26") (pintype "passive"))
    )
    (net (code "193") (name "unconnected-(U8-NC_2-Pad21)") (class "Default")
      (node (ref "U8") (pin "21") (pinfunction "NC_2_21") (pintype "passive"))
    )
    (net (code "194") (name "unconnected-(U8-NC_3-Pad23)") (class "Default")
      (node (ref "U8") (pin "23") (pinfunction "NC_3_23") (pintype "passive"))
    )
    (net (code "195") (name "unconnected-(U8-NC_4-Pad24)") (class "Default")
      (node (ref "U8") (pin "24") (pinfunction "NC_4_24") (pintype "passive"))
    )
    (net (code "196") (name "unconnected-(U8-NC_5-Pad25)") (class "Default")
      (node (ref "U8") (pin "25") (pinfunction "NC_5_25") (pintype "passive"))
    )
    (net (code "197") (name "unconnected-(U9-NC-Pad26)") (class "Default")
      (node (ref "U9") (pin "26") (pinfunction "NC_26") (pintype "passive"))
    )
    (net (code "198") (name "unconnected-(U9-NC_2-Pad21)") (class "Default")
      (node (ref "U9") (pin "21") (pinfunction "NC_2_21") (pintype "passive"))
    )
    (net (code "199") (name "unconnected-(U9-NC_3-Pad23)") (class "Default")
      (node (ref "U9") (pin "23") (pinfunction "NC_3_23") (pintype "passive"))
    )
    (net (code "200") (name "unconnected-(U9-NC_4-Pad24)") (class "Default")
      (node (ref "U9") (pin "24") (pinfunction "NC_4_24") (pintype "passive"))
    )
    (net (code "201") (name "unconnected-(U9-NC_5-Pad25)") (class "Default")
      (node (ref "U9") (pin "25") (pinfunction "NC_5_25") (pintype "passive"))
    )
    (net (code "202") (name "unconnected-(U10-NC-Pad26)") (class "Default")
      (node (ref "U10") (pin "26") (pinfunction "NC_26") (pintype "passive"))
    )
    (net (code "203") (name "unconnected-(U10-NC_2-Pad21)") (class "Default")
      (node (ref "U10") (pin "21") (pinfunction "NC_2_21") (pintype "passive"))
    )
    (net (code "204") (name "unconnected-(U10-NC_3-Pad23)") (class "Default")
      (node (ref "U10") (pin "23") (pinfunction "NC_3_23") (pintype "passive"))
    )
    (net (code "205") (name "unconnected-(U10-NC_4-Pad24)") (class "Default")
      (node (ref "U10") (pin "24") (pinfunction "NC_4_24") (pintype "passive"))
    )
    (net (code "206") (name "unconnected-(U10-NC_5-Pad25)") (class "Default")
      (node (ref "U10") (pin "25") (pinfunction "NC_5_25") (pintype "passive"))
    )
    (net (code "207") (name "unconnected-(U11-NC-Pad26)") (class "Default")
      (node (ref "U11") (pin "26") (pinfunction "NC_26") (pintype "passive"))
    )
    (net (code "208") (name "unconnected-(U11-NC_2-Pad21)") (class "Default")
      (node (ref "U11") (pin "21") (pinfunction "NC_2_21") (pintype "passive"))
    )
    (net (code "209") (name "unconnected-(U11-NC_3-Pad23)") (class "Default")
      (node (ref "U11") (pin "23") (pinfunction "NC_3_23") (pintype "passive"))
    )
    (net (code "210") (name "unconnected-(U11-NC_4-Pad24)") (class "Default")
      (node (ref "U11") (pin "24") (pinfunction "NC_4_24") (pintype "passive"))
    )
    (net (code "211") (name "unconnected-(U11-NC_5-Pad25)") (class "Default")
      (node (ref "U11") (pin "25") (pinfunction "NC_5_25") (pintype "passive"))
    )
    (net (code "212") (name "unconnected-(U12-NC-Pad26)") (class "Default")
      (node (ref "U12") (pin "26") (pinfunction "NC_26") (pintype "passive"))
    )
    (net (code "213") (name "unconnected-(U12-NC_2-Pad21)") (class "Default")
      (node (ref "U12") (pin "21") (pinfunction "NC_2_21") (pintype "passive"))
    )
    (net (code "214") (name "unconnected-(U12-NC_3-Pad23)") (class "Default")
      (node (ref "U12") (pin "23") (pinfunction "NC_3_23") (pintype "passive"))
    )
    (net (code "215") (name "unconnected-(U12-NC_4-Pad24)") (class "Default")
      (node (ref "U12") (pin "24") (pinfunction "NC_4_24") (pintype "passive"))
    )
    (net (code "216") (name "unconnected-(U12-NC_5-Pad25)") (class "Default")
      (node (ref "U12") (pin "25") (pinfunction "NC_5_25") (pintype "passive"))
    )
    (net (code "217") (name "unconnected-(U13-NC-Pad26)") (class "Default")
      (node (ref "U13") (pin "26") (pinfunction "NC_26") (pintype "passive"))
    )
    (net (code "218") (name "unconnected-(U13-NC_2-Pad21)") (class "Default")
      (node (ref "U13") (pin "21") (pinfunction "NC_2_21") (pintype "passive"))
    )
    (net (code "219") (name "unconnected-(U13-NC_3-Pad23)") (class "Default")
      (node (ref "U13") (pin "23") (pinfunction "NC_3_23") (pintype "passive"))
    )
    (net (code "220") (name "unconnected-(U13-NC_4-Pad24)") (class "Default")
      (node (ref "U13") (pin "24") (pinfunction "NC_4_24") (pintype "passive"))
    )
    (net (code "221") (name "unconnected-(U13-NC_5-Pad25)") (class "Default")
      (node (ref "U13") (pin "25") (pinfunction "NC_5_25") (pintype "passive"))
    )
    (net (code "222") (name "unconnected-(U14-1B2-PadP$3)") (class "Default")
      (node (ref "U14") (pin "P$3") (pinfunction "1B2_P$3") (pintype "bidirectional"))
    )
    (net (code "223") (name "unconnected-(U14-2B2-PadP$6)") (class "Default")
      (node (ref "U14") (pin "P$6") (pinfunction "2B2_P$6") (pintype "bidirectional"))
    )
    (net (code "224") (name "unconnected-(U14-3B2-PadP$10)") (class "Default")
      (node (ref "U14") (pin "P$10") (pinfunction "3B2_P$10") (pintype "bidirectional"))
    )
    (net (code "225") (name "unconnected-(U14-4A-PadP$12)") (class "Default")
      (node (ref "U14") (pin "P$12") (pinfunction "4A_P$12") (pintype "bidirectional"))
    )
    (net (code "226") (name "unconnected-(U14-4B1-PadP$14)") (class "Default")
      (node (ref "U14") (pin "P$14") (pinfunction "4B1_P$14") (pintype "bidirectional"))
    )
    (net (code "227") (name "unconnected-(U14-4B2-PadP$13)") (class "Default")
      (node (ref "U14") (pin "P$13") (pinfunction "4B2_P$13") (pintype "bidirectional"))
    )
    (net (code "228") (name "unconnected-(U15-NC-Pad26)") (class "Default")
      (node (ref "U15") (pin "26") (pinfunction "NC_26") (pintype "passive"))
    )
    (net (code "229") (name "unconnected-(U15-NC_2-Pad21)") (class "Default")
      (node (ref "U15") (pin "21") (pinfunction "NC_2_21") (pintype "passive"))
    )
    (net (code "230") (name "unconnected-(U15-NC_3-Pad23)") (class "Default")
      (node (ref "U15") (pin "23") (pinfunction "NC_3_23") (pintype "passive"))
    )
    (net (code "231") (name "unconnected-(U15-NC_4-Pad24)") (class "Default")
      (node (ref "U15") (pin "24") (pinfunction "NC_4_24") (pintype "passive"))
    )
    (net (code "232") (name "unconnected-(U15-NC_5-Pad25)") (class "Default")
      (node (ref "U15") (pin "25") (pinfunction "NC_5_25") (pintype "passive"))
    )
    (net (code "233") (name "unconnected-(U16-NC-Pad26)") (class "Default")
      (node (ref "U16") (pin "26") (pinfunction "NC_26") (pintype "passive"))
    )
    (net (code "234") (name "unconnected-(U16-NC_2-Pad21)") (class "Default")
      (node (ref "U16") (pin "21") (pinfunction "NC_2_21") (pintype "passive"))
    )
    (net (code "235") (name "unconnected-(U16-NC_3-Pad23)") (class "Default")
      (node (ref "U16") (pin "23") (pinfunction "NC_3_23") (pintype "passive"))
    )
    (net (code "236") (name "unconnected-(U16-NC_4-Pad24)") (class "Default")
      (node (ref "U16") (pin "24") (pinfunction "NC_4_24") (pintype "passive"))
    )
    (net (code "237") (name "unconnected-(U16-NC_5-Pad25)") (class "Default")
      (node (ref "U16") (pin "25") (pinfunction "NC_5_25") (pintype "passive"))
    )
    (net (code "238") (name "unconnected-(U17-NC-Pad26)") (class "Default")
      (node (ref "U17") (pin "26") (pinfunction "NC_26") (pintype "passive"))
    )
    (net (code "239") (name "unconnected-(U17-NC_2-Pad21)") (class "Default")
      (node (ref "U17") (pin "21") (pinfunction "NC_2_21") (pintype "passive"))
    )
    (net (code "240") (name "unconnected-(U17-NC_3-Pad23)") (class "Default")
      (node (ref "U17") (pin "23") (pinfunction "NC_3_23") (pintype "passive"))
    )
    (net (code "241") (name "unconnected-(U17-NC_4-Pad24)") (class "Default")
      (node (ref "U17") (pin "24") (pinfunction "NC_4_24") (pintype "passive"))
    )
    (net (code "242") (name "unconnected-(U17-NC_5-Pad25)") (class "Default")
      (node (ref "U17") (pin "25") (pinfunction "NC_5_25") (pintype "passive"))
    )
  )
)
